# 519_jetson_nano_020001.net
KiCad netlist of a schematic drawn in EAGLE
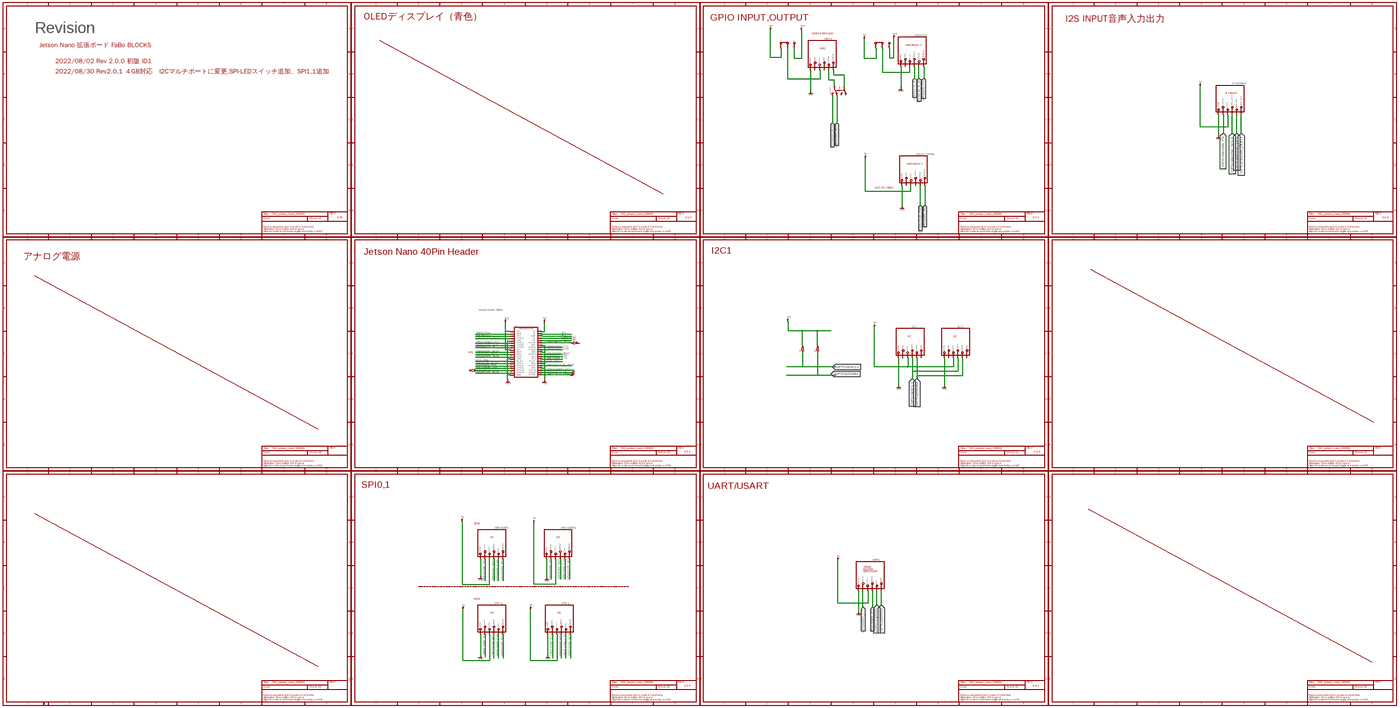
[diagram p0: schematic, sheet 1, overview]
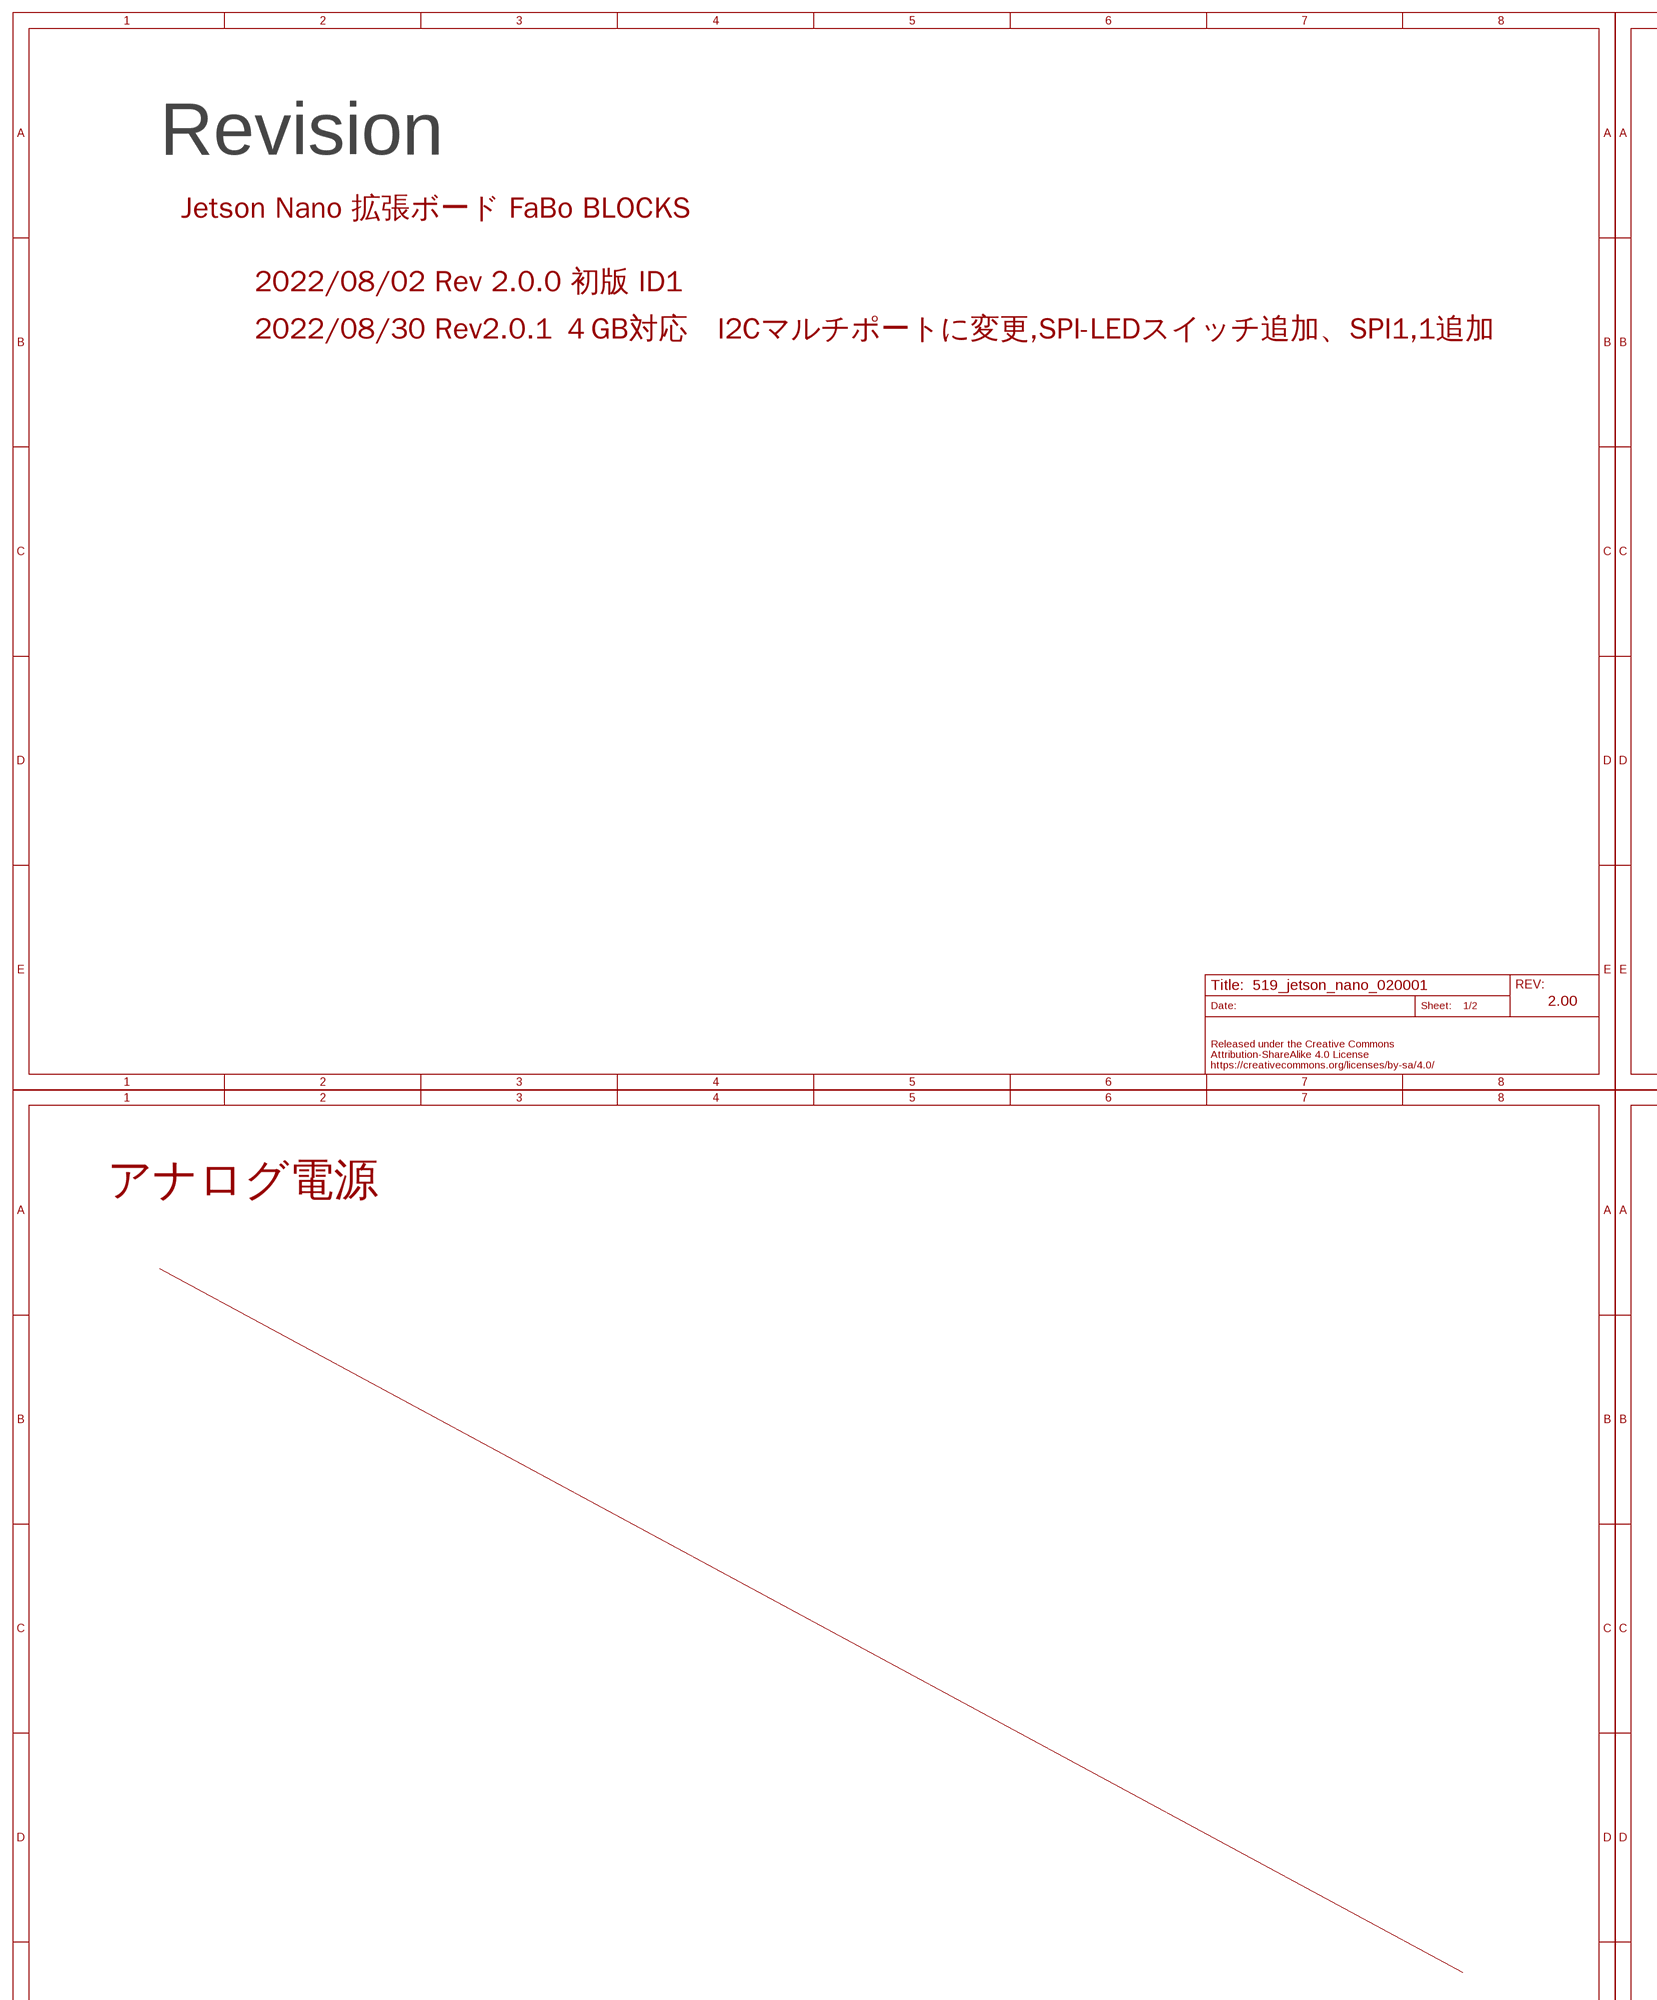
[diagram p1: schematic, sheet 1, part 1 of 8]
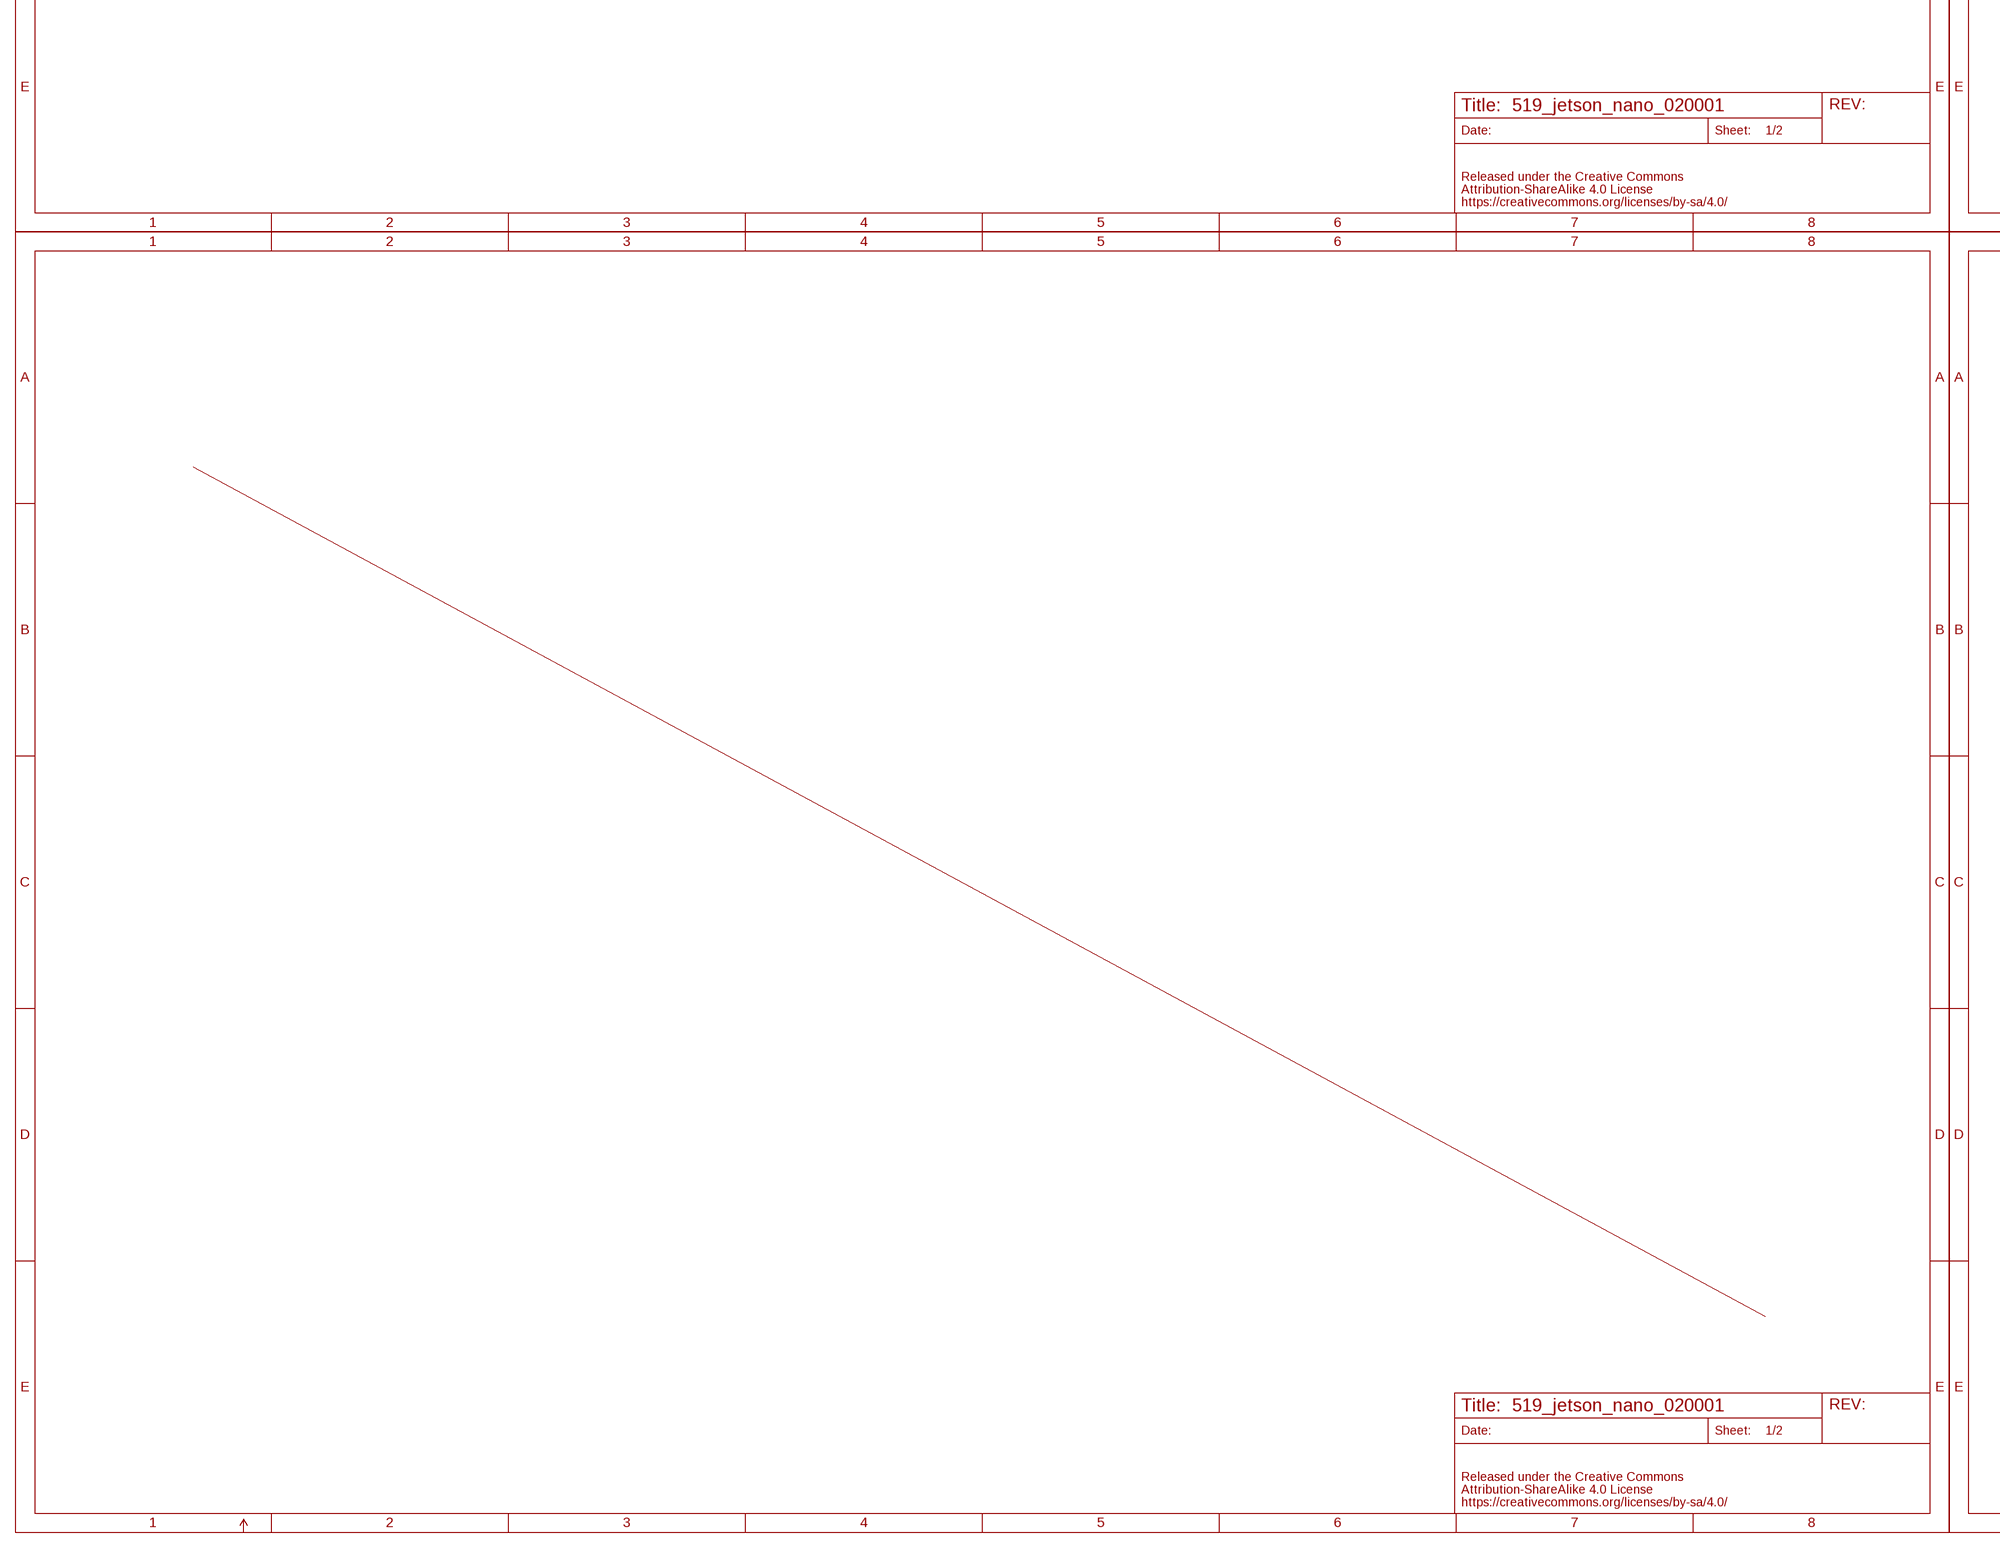
[diagram p2: schematic, sheet 1, part 2 of 8]
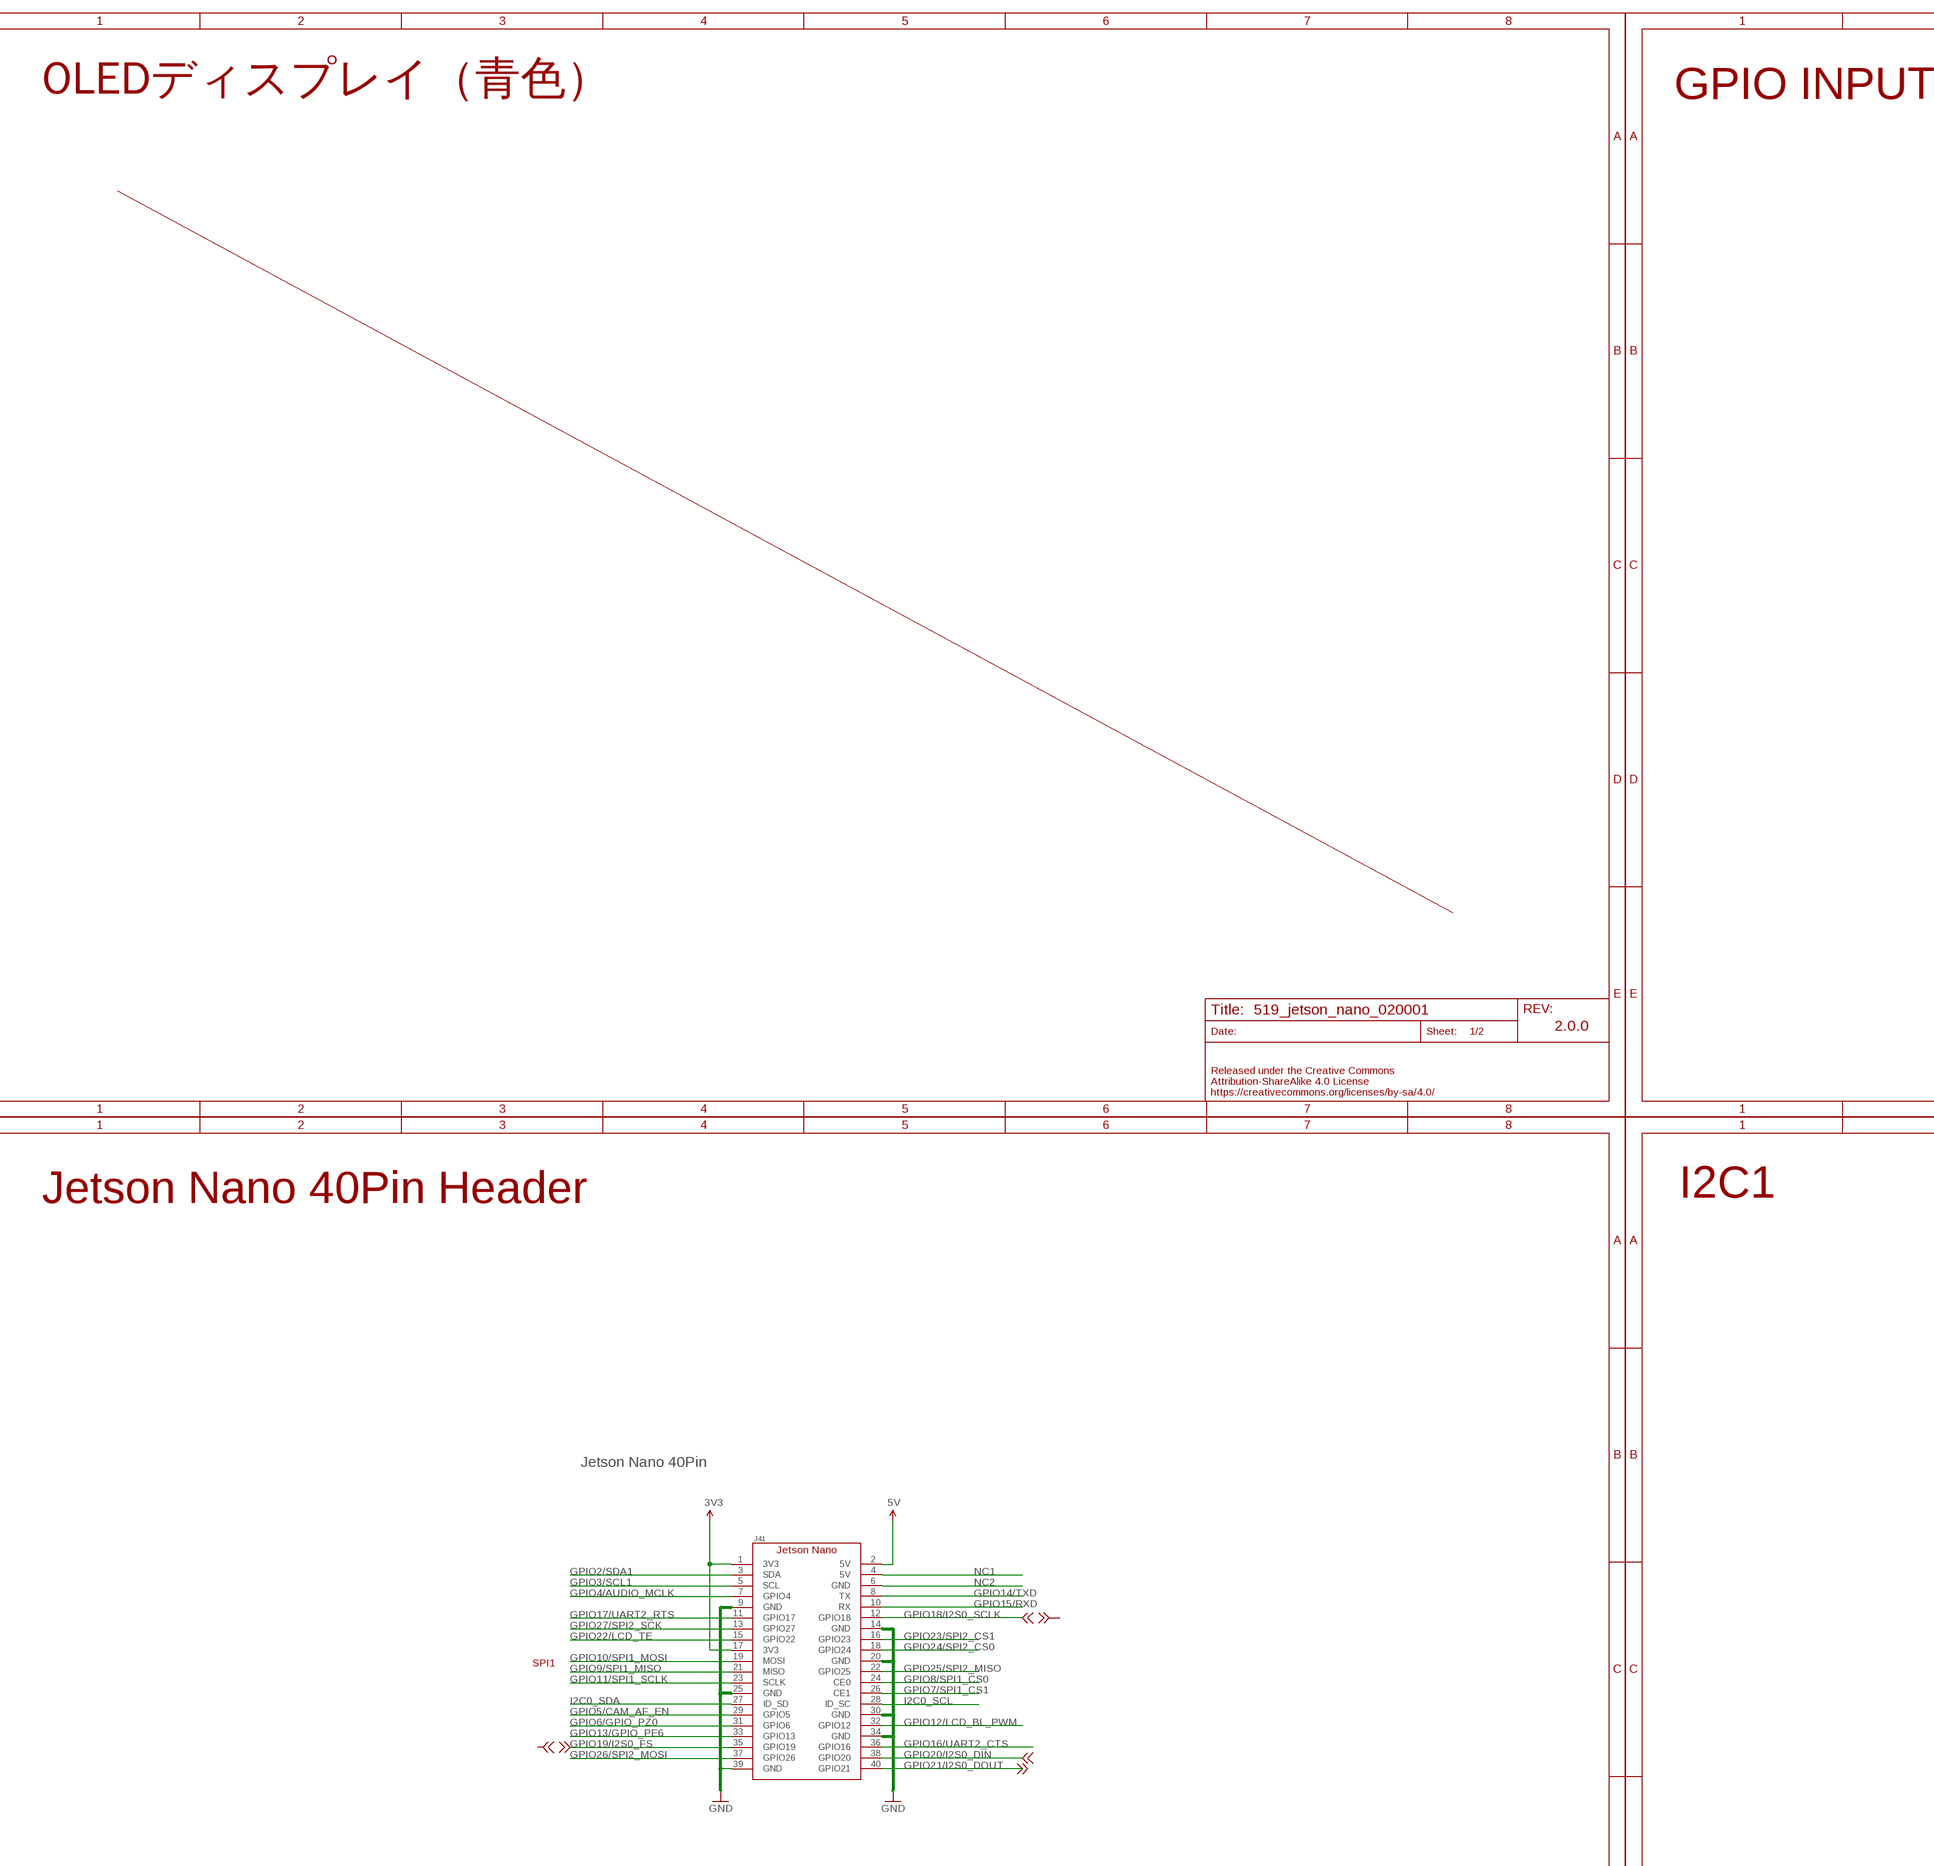
[diagram p3: schematic, sheet 1, part 3 of 8]
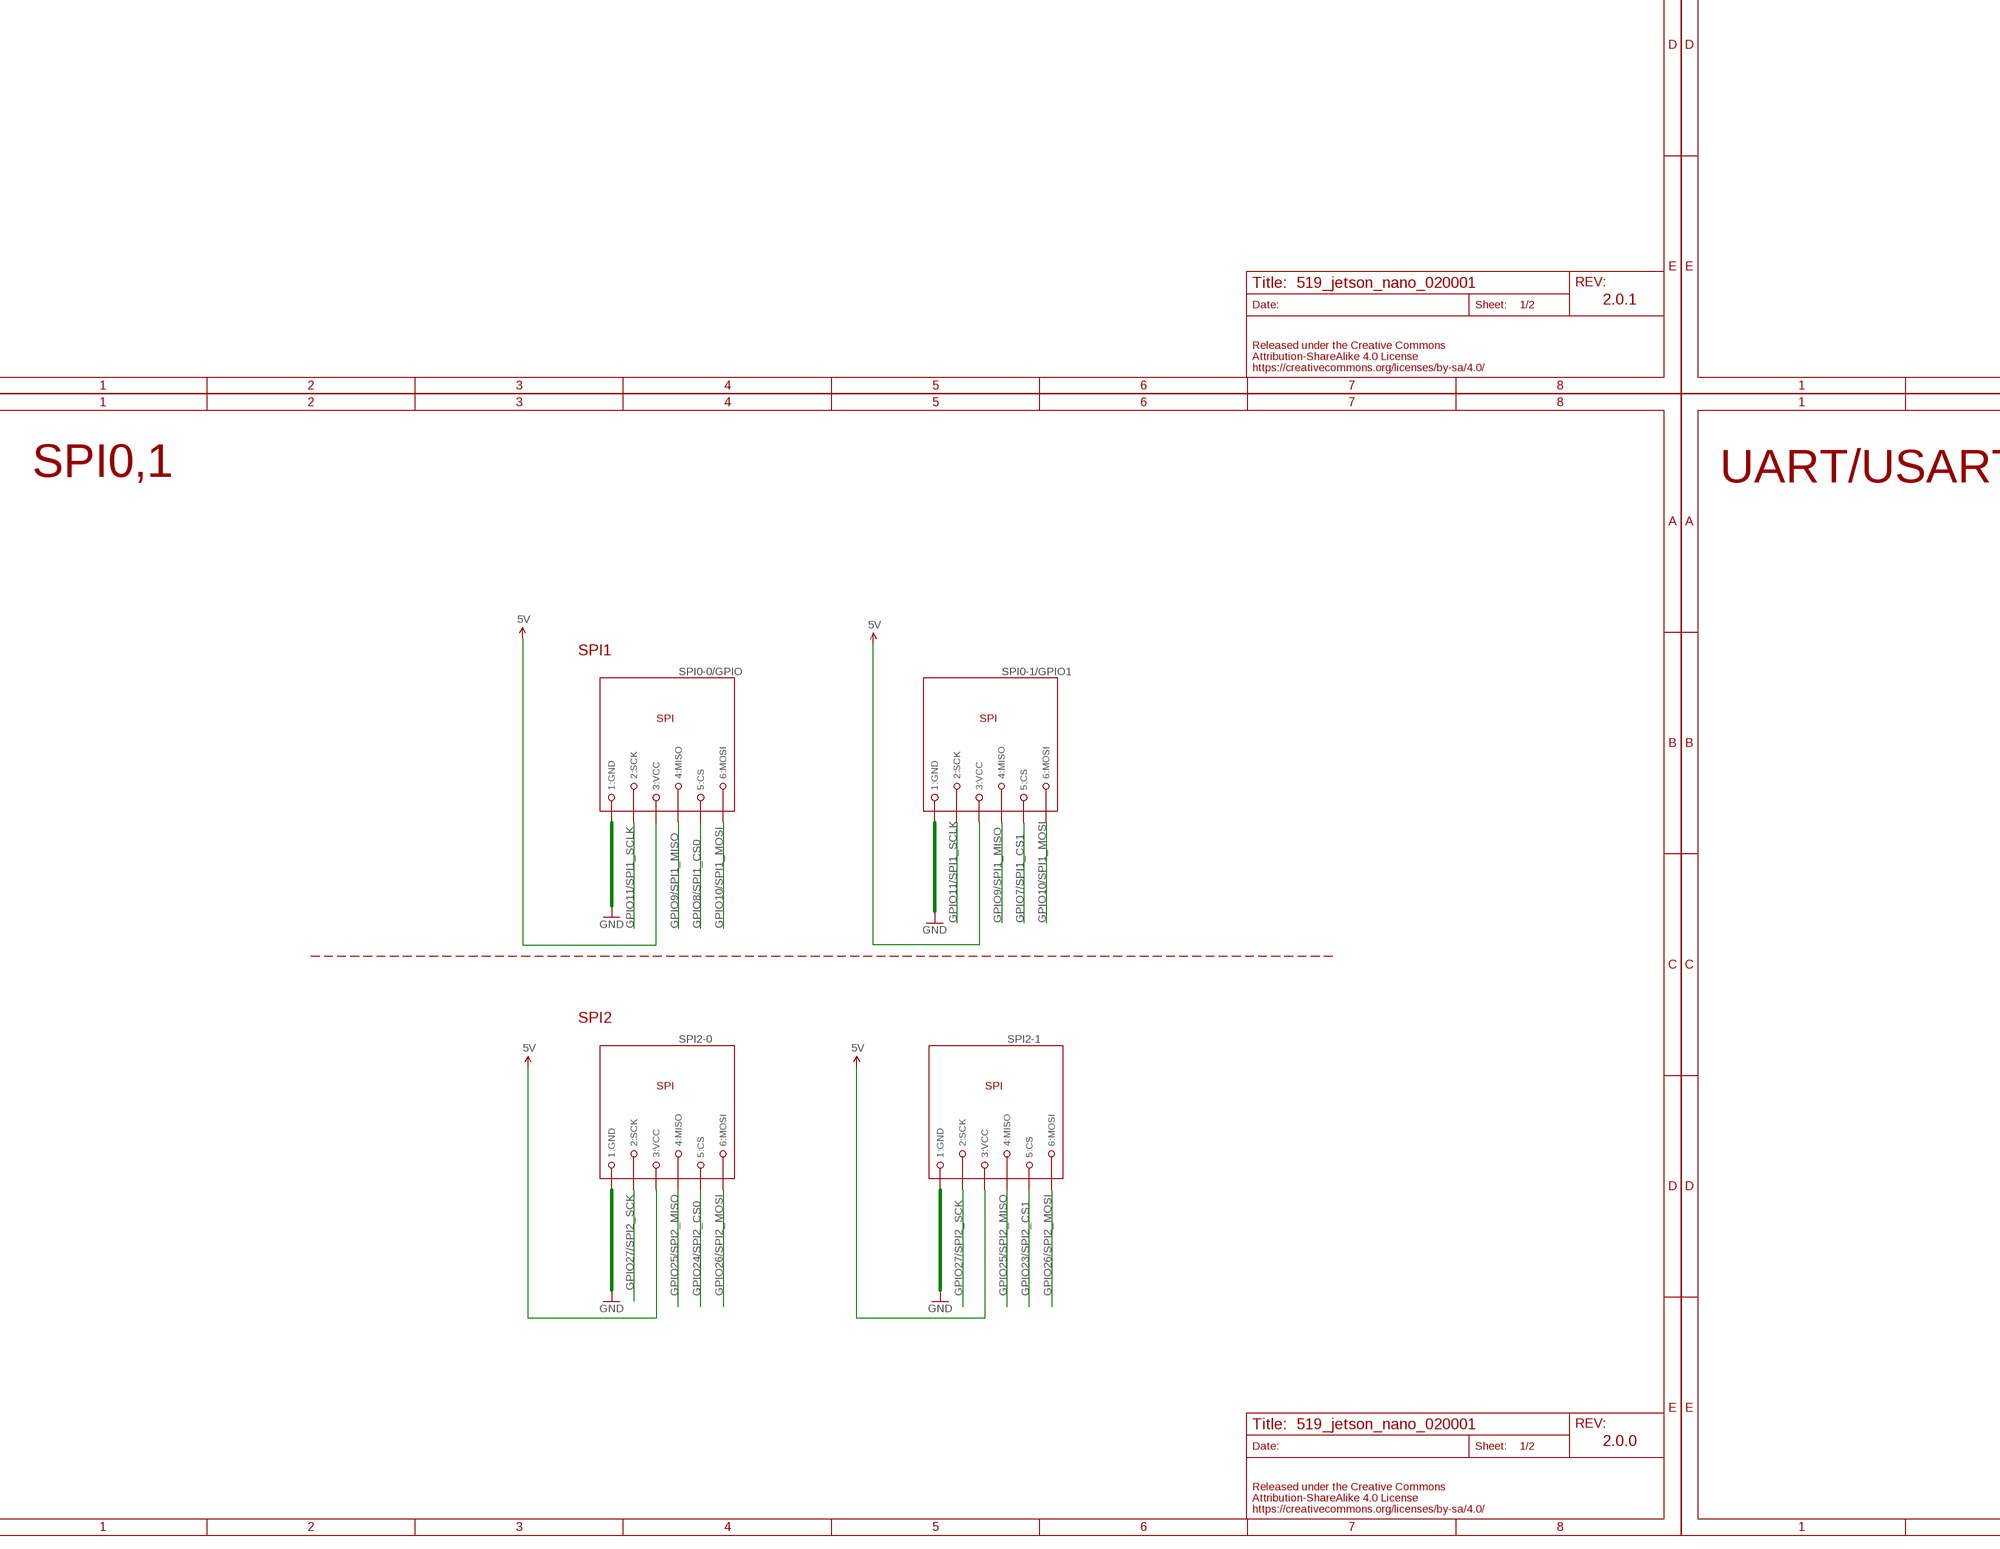
[diagram p4: schematic, sheet 1, part 4 of 8]
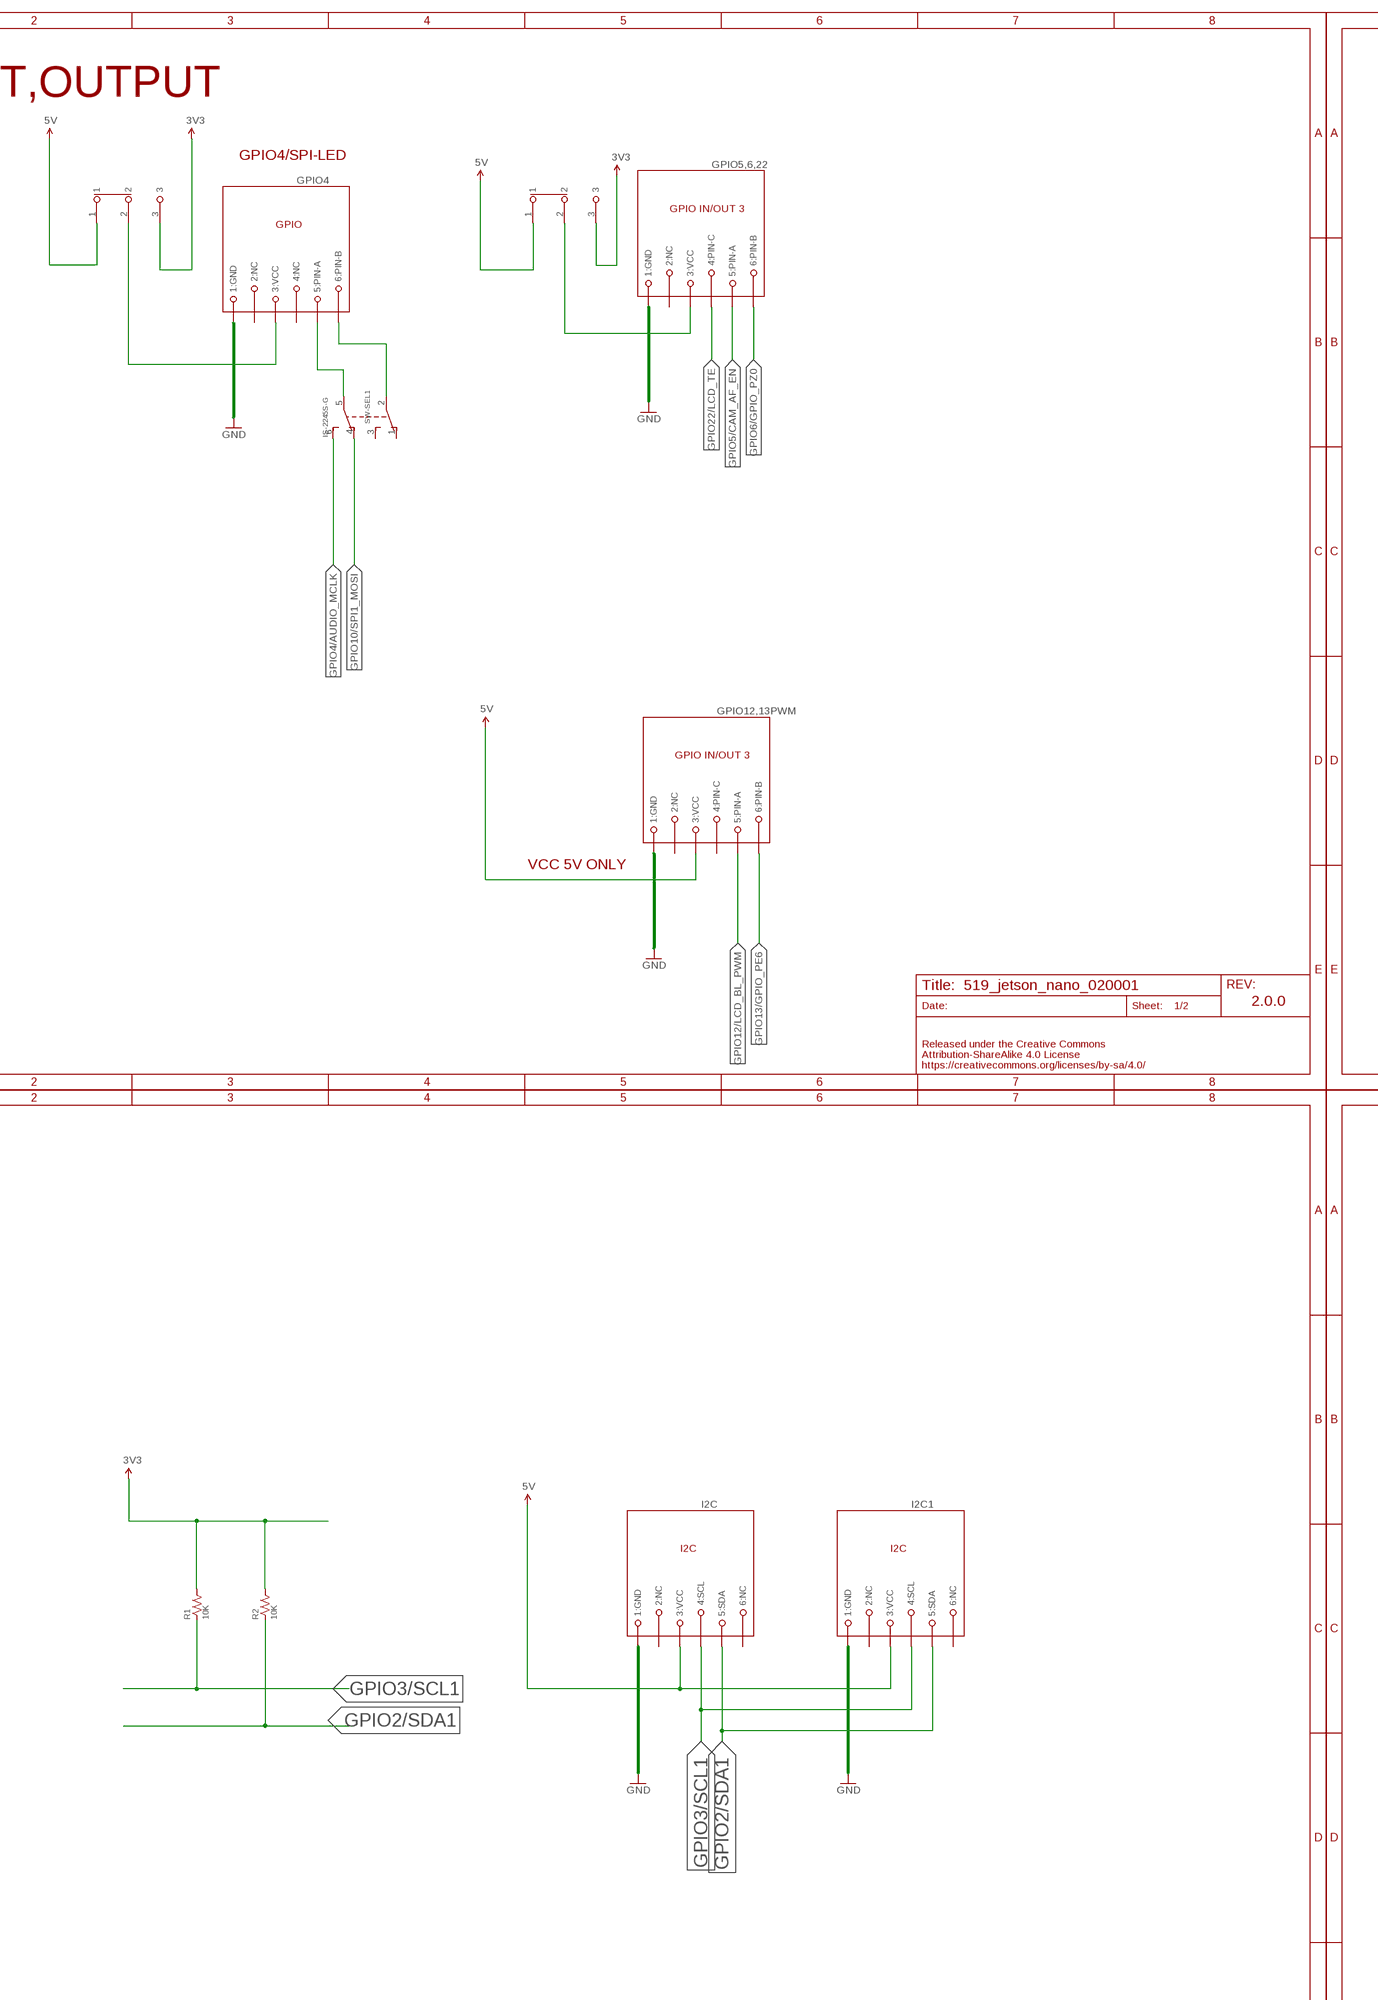
[diagram p5: schematic, sheet 1, part 5 of 8]
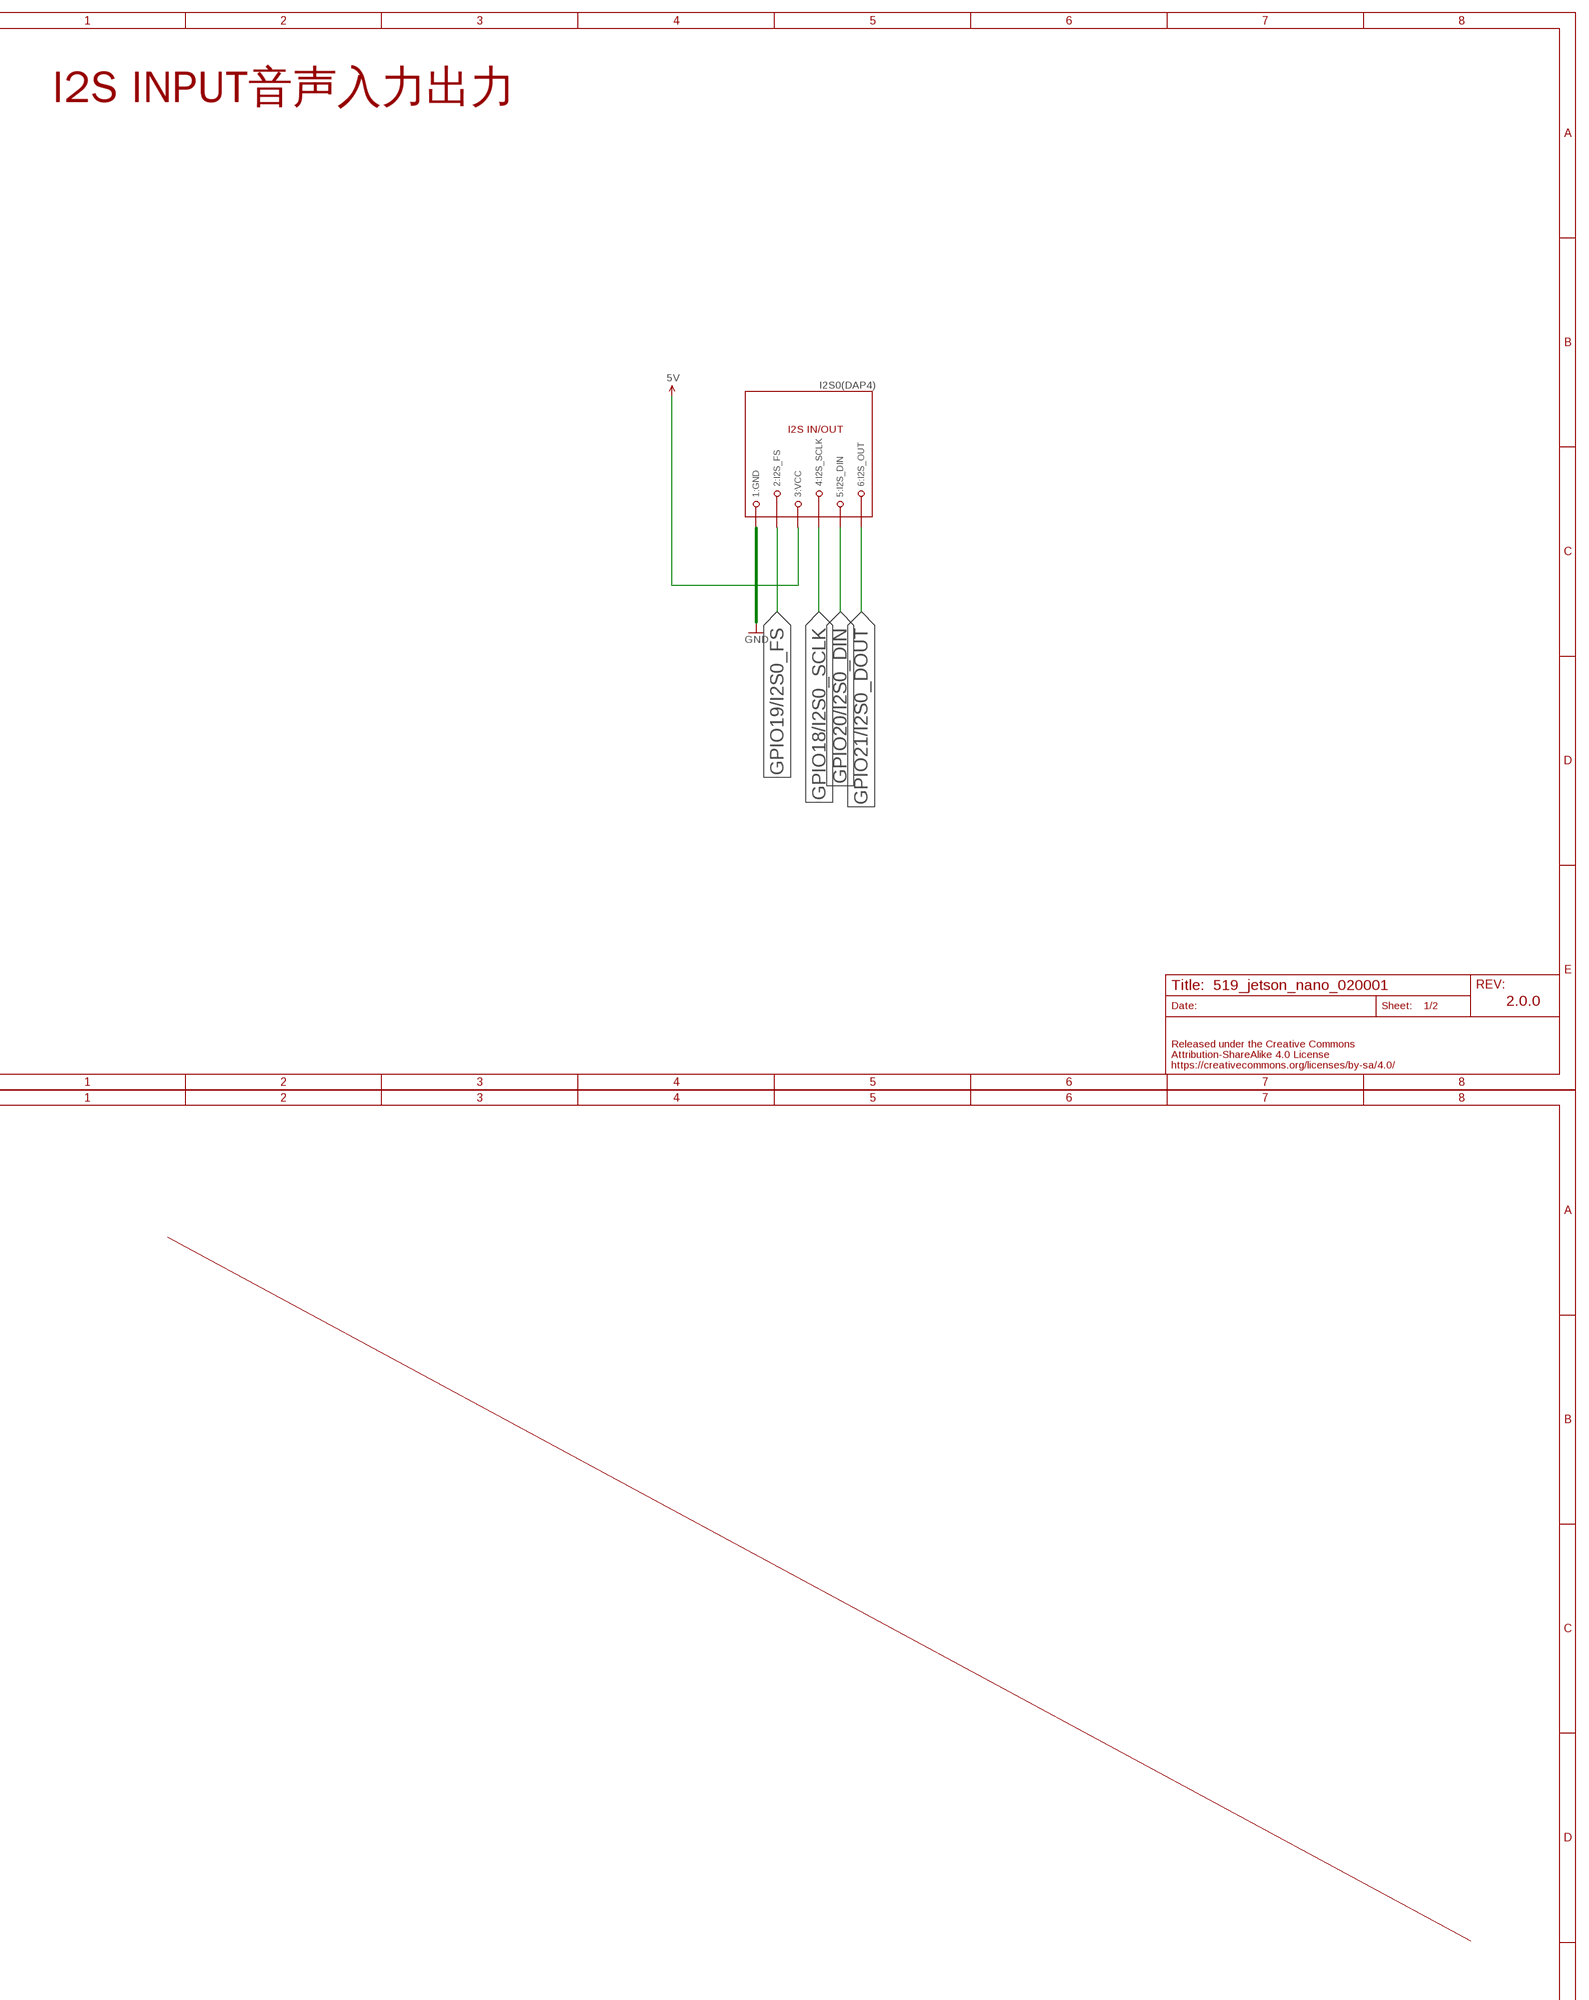
[diagram p6: schematic, sheet 1, part 6 of 8]
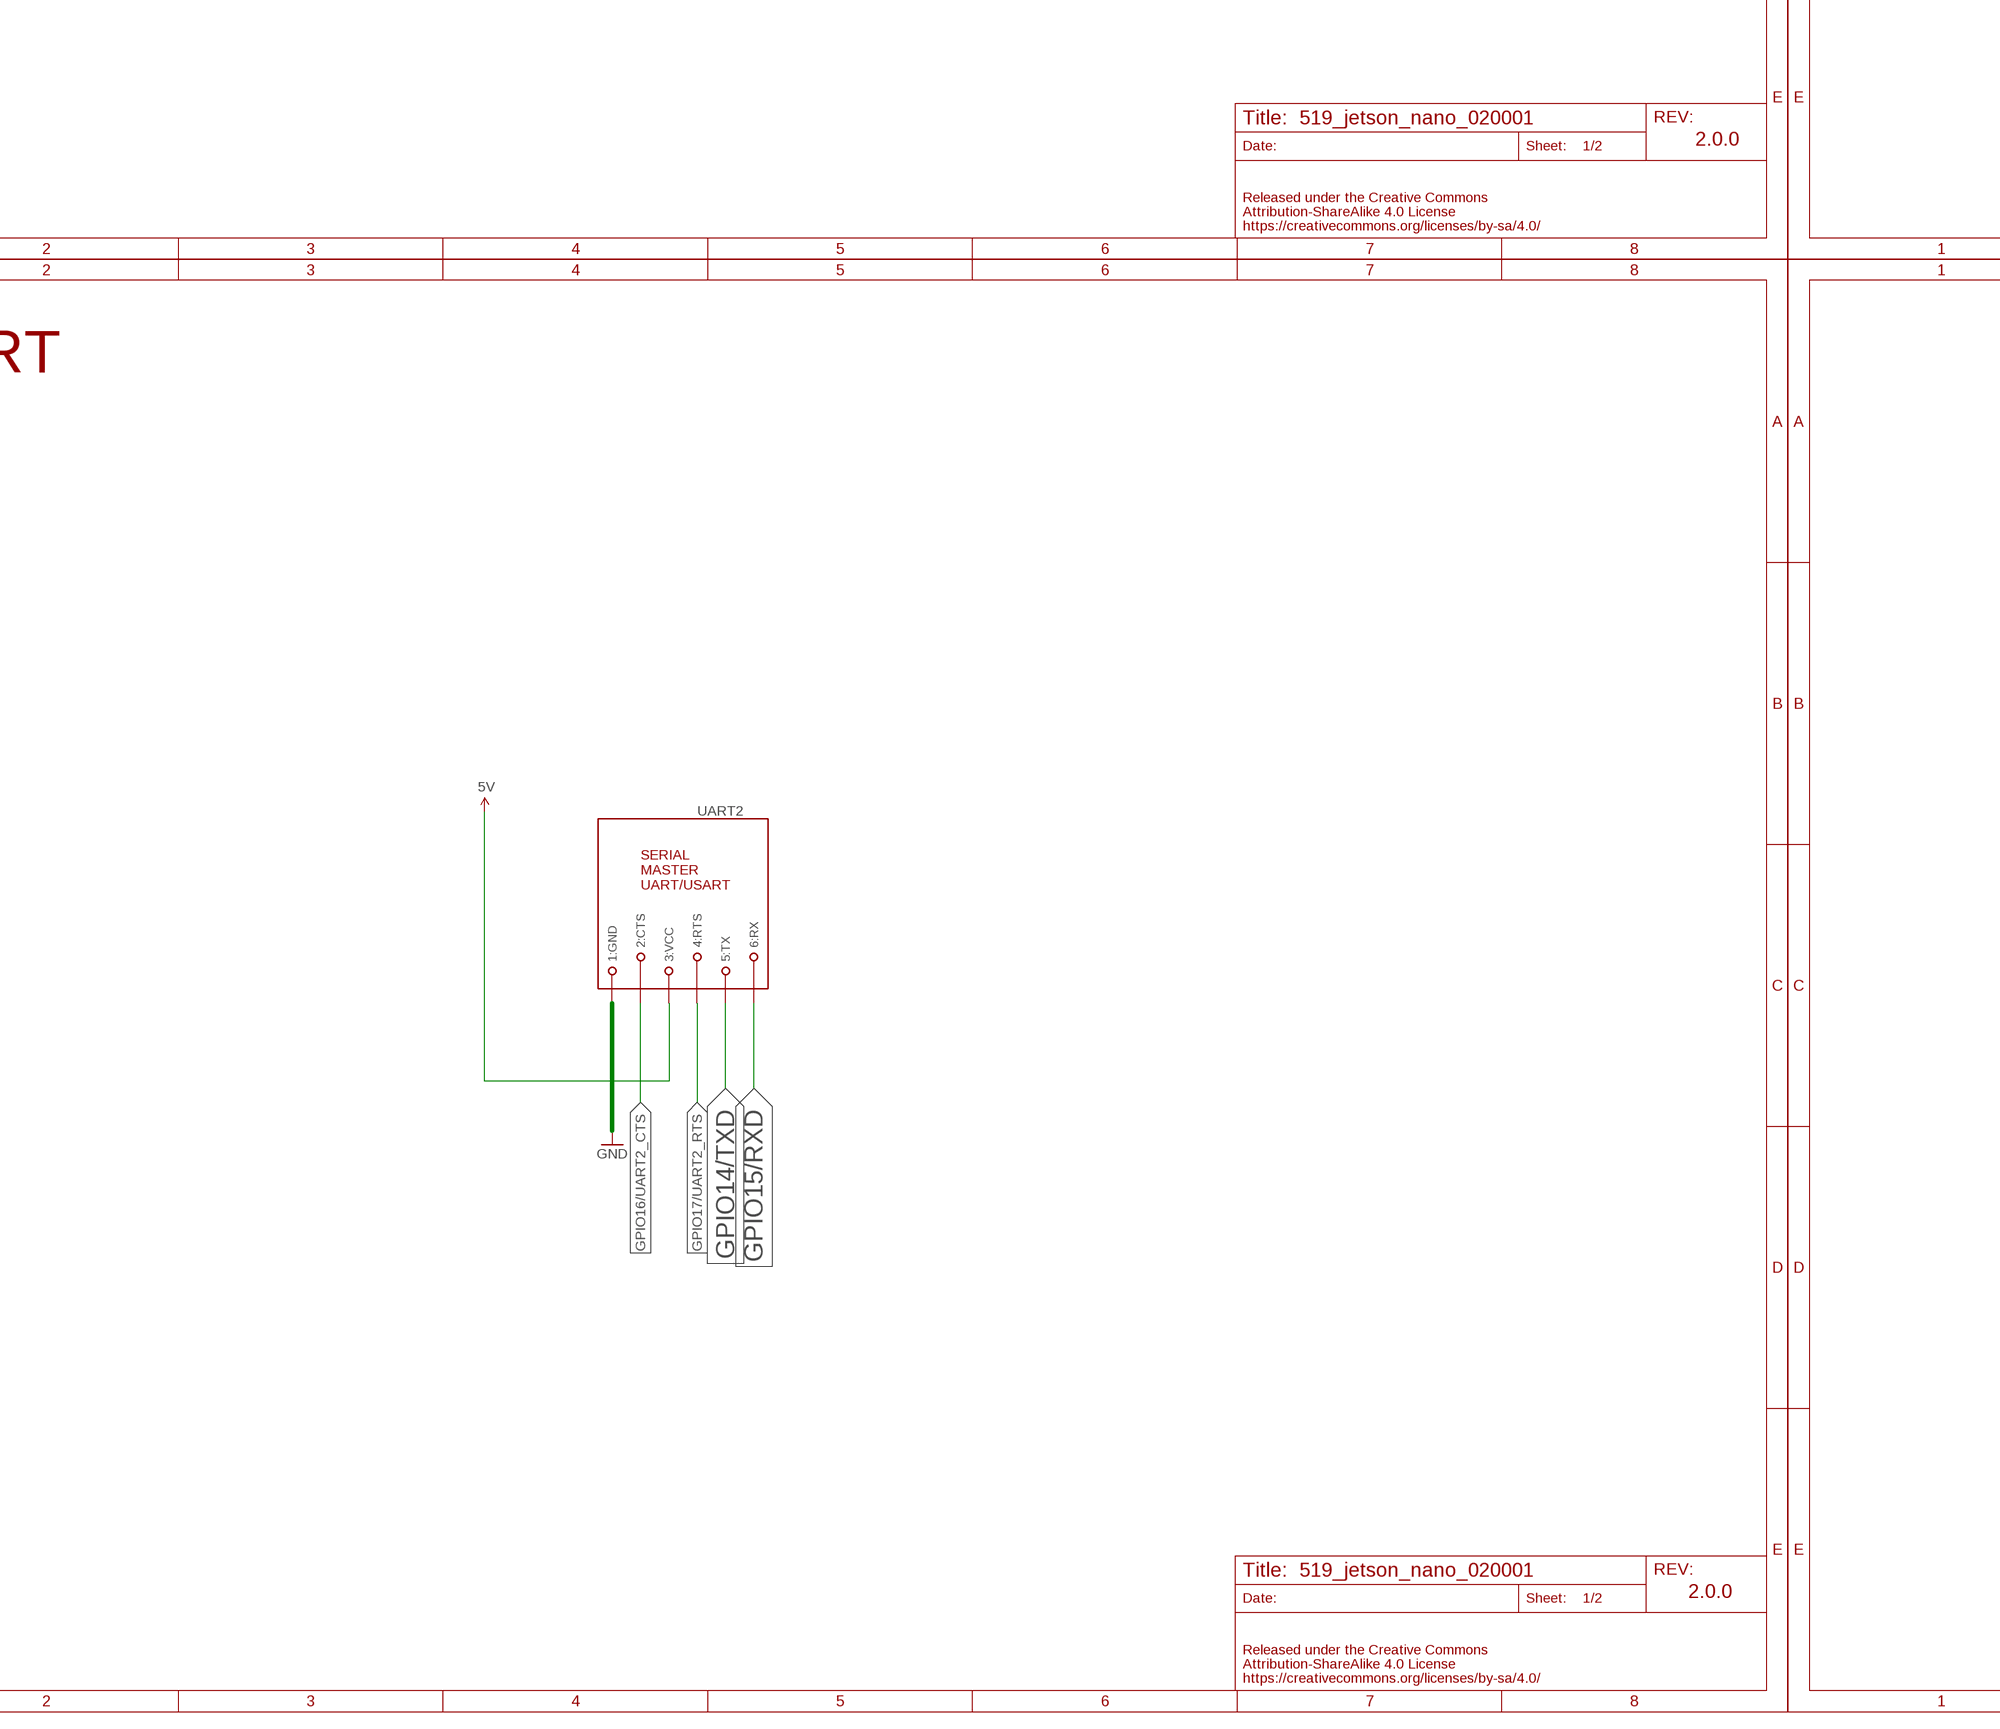
[diagram p7: schematic, sheet 1, part 7 of 8]
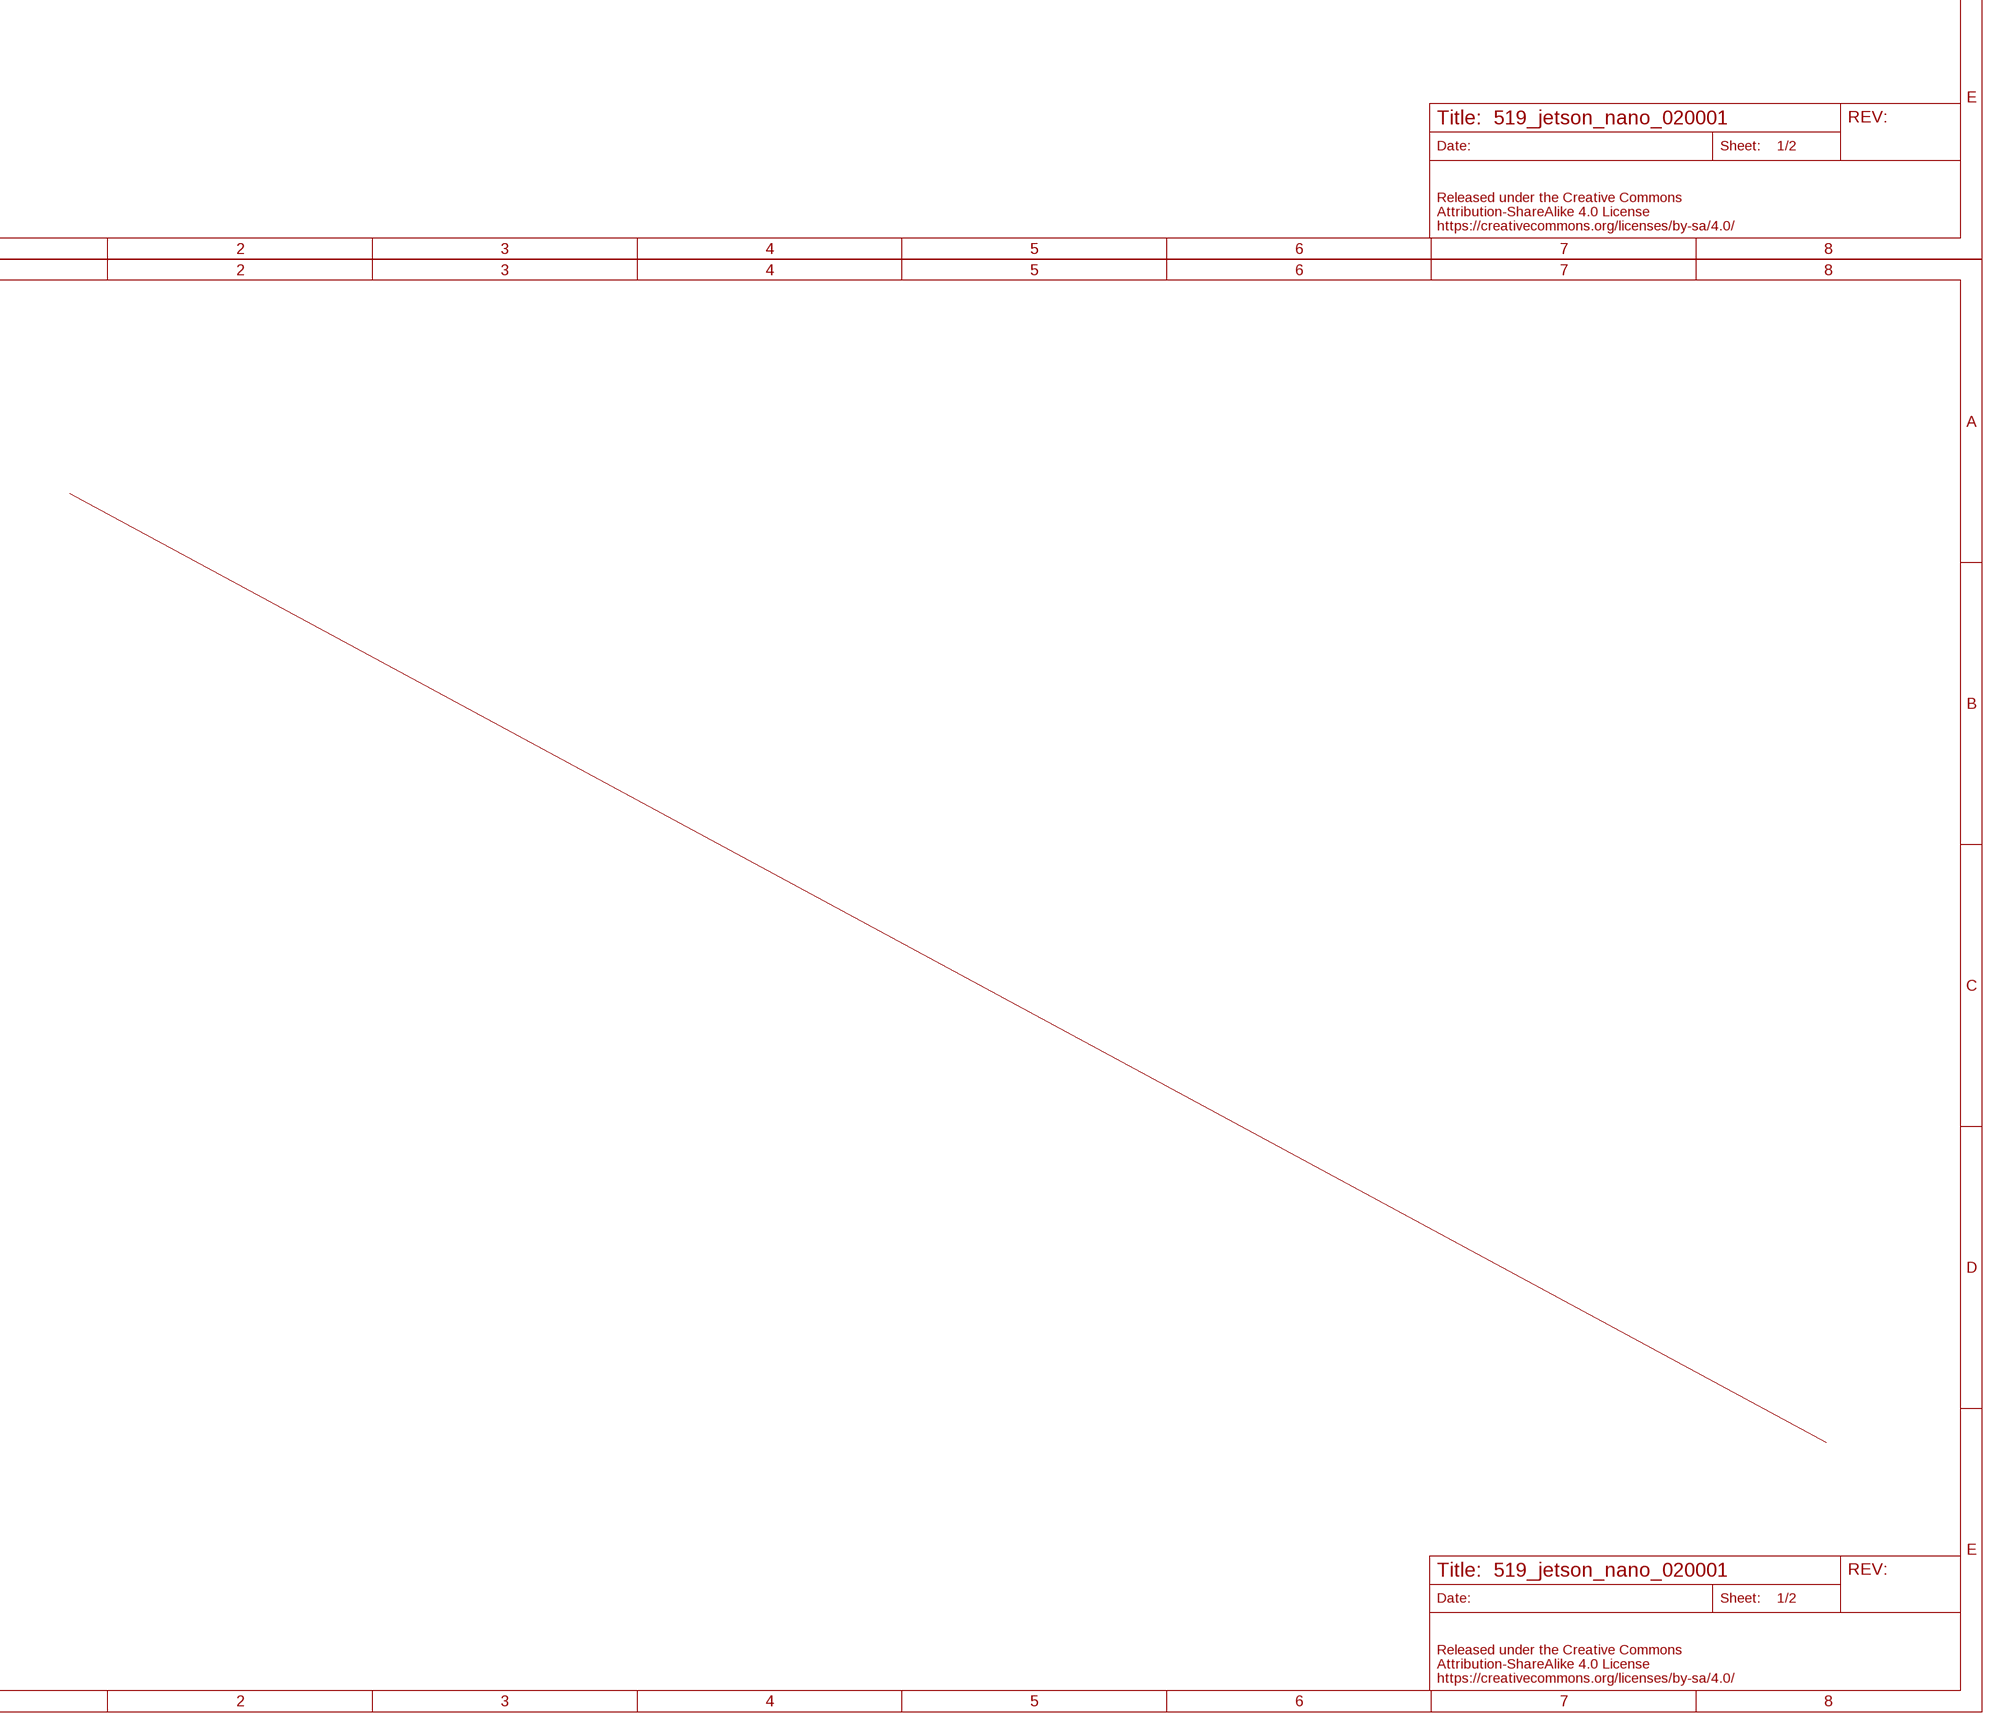
[diagram p8: schematic, sheet 1, part 8 of 8]
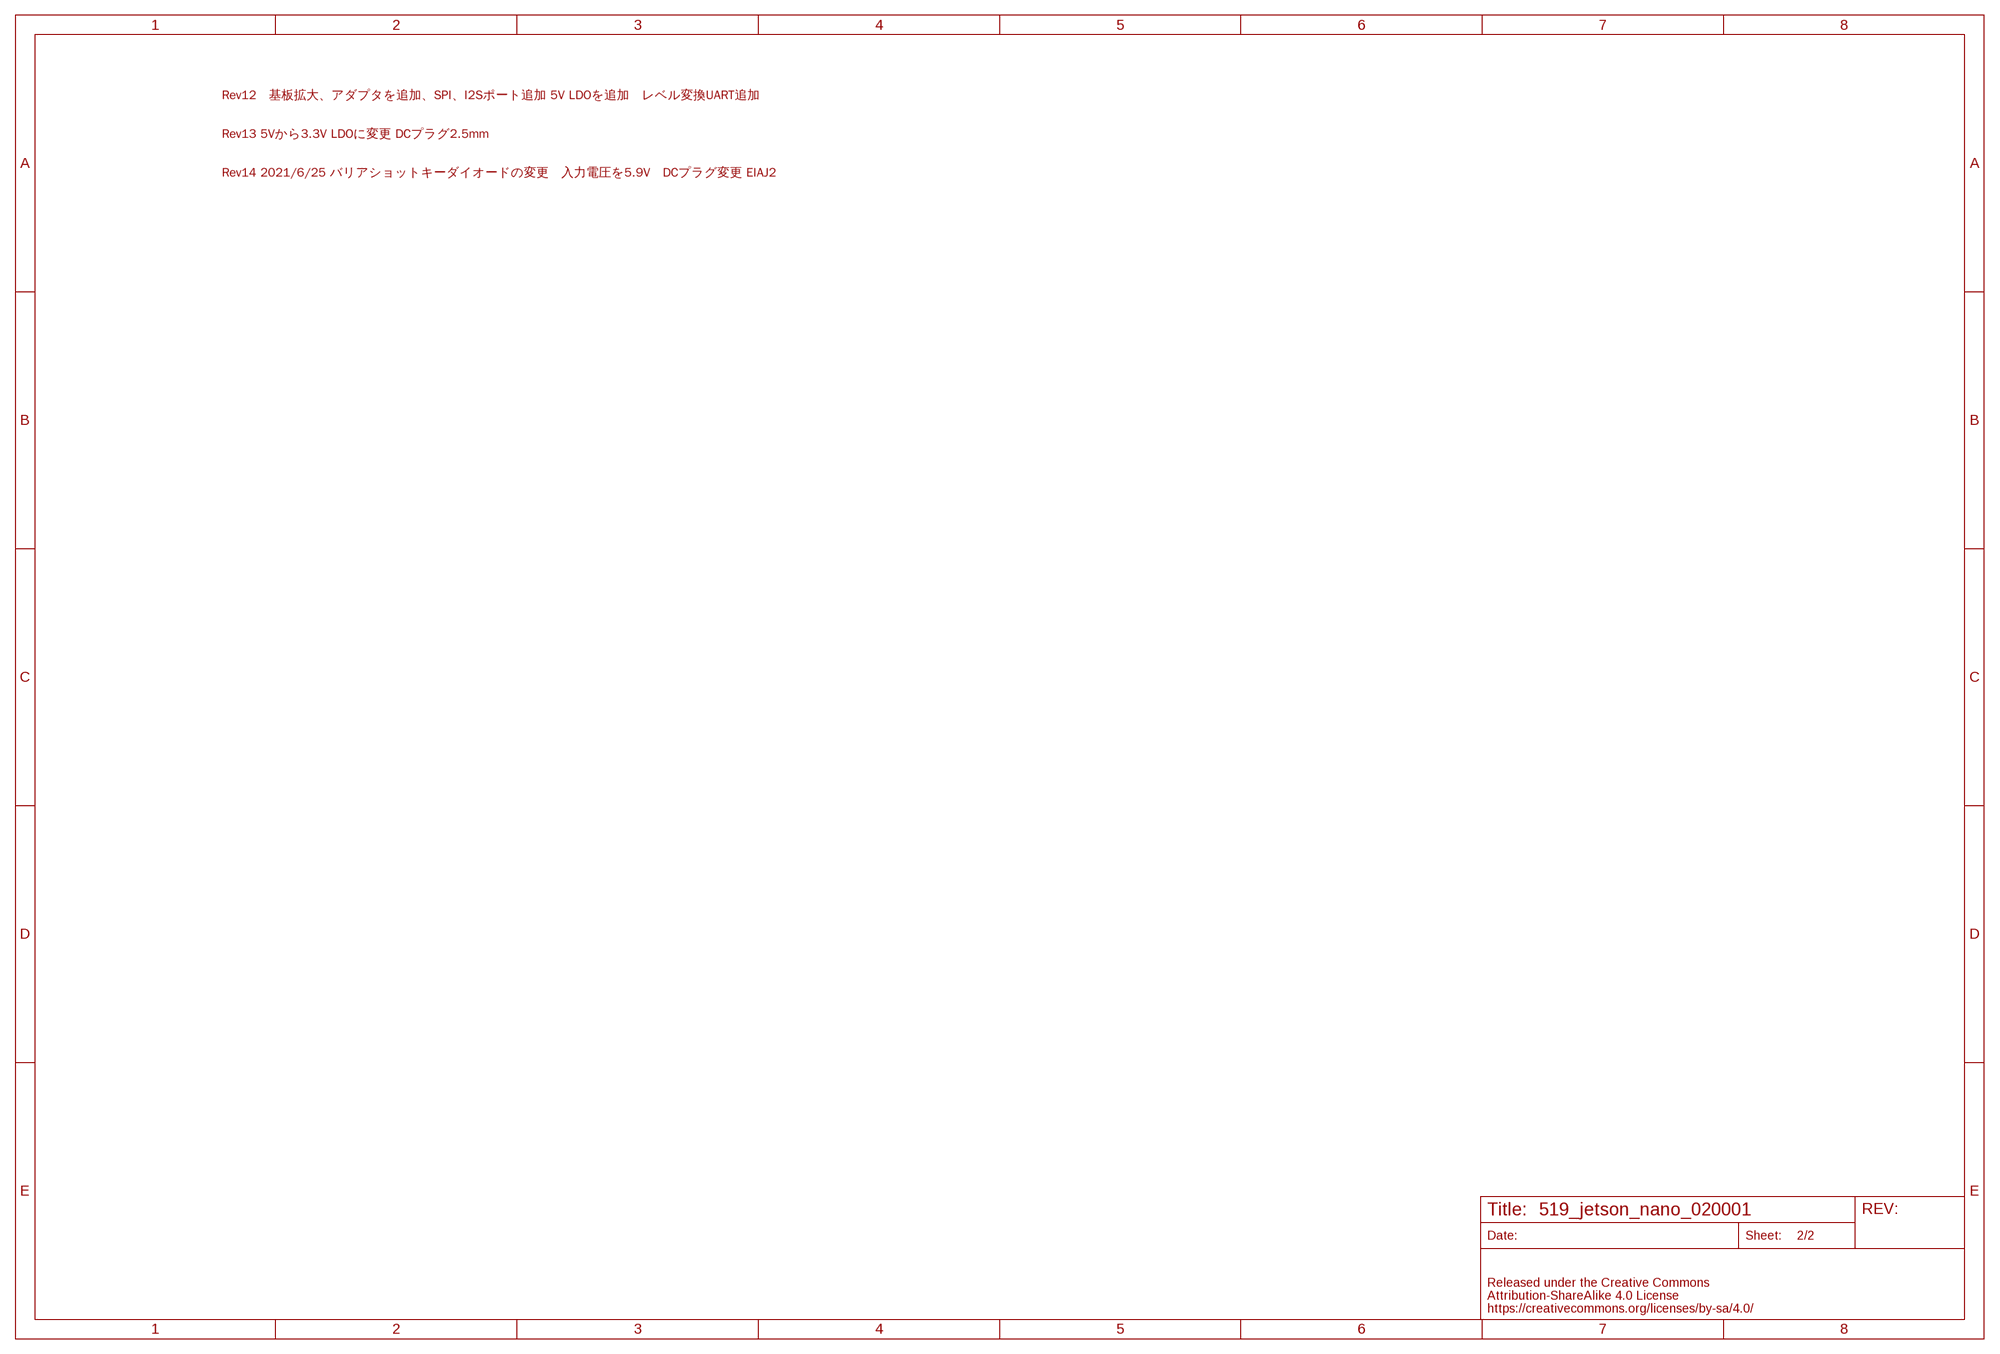
[diagram p9: schematic, sheet 2]

(export (version "E")
  (design (tool "Eeschema 10.0.6"))
  (components
    (comp (ref "GPIO4")
      (value "MODULAR-JACK-6P-RJ11_GPIO")
      (footprint "eagle-import:7002-6PXC-X")
      (libsource (lib "eagle-import") (part "MODULAR-JACK-6P-RJ11_GPIO"))
    )
    (comp (ref "GPIO5,6,22")
      (value "MODULAR-JACK-6P-RJ11_GPIO3")
      (footprint "eagle-import:7002-6PXC-X")
      (libsource (lib "eagle-import") (part "MODULAR-JACK-6P-RJ11_GPIO3"))
    )
    (comp (ref "GPIO12,13PWM")
      (value "MODULAR-JACK-6P-RJ11_GPIO3")
      (footprint "eagle-import:7002-6PXC-X")
      (libsource (lib "eagle-import") (part "MODULAR-JACK-6P-RJ11_GPIO3"))
    )
    (comp (ref "I2C")
      (value "MODULAR-JACK-6P-RJ11_I2C")
      (footprint "eagle-import:7002-6PXC-X")
      (libsource (lib "eagle-import") (part "MODULAR-JACK-6P-RJ11_I2C"))
    )
    (comp (ref "I2C1")
      (value "MODULAR-JACK-6P-RJ11_I2C")
      (footprint "eagle-import:7002-6PXC-X")
      (libsource (lib "eagle-import") (part "MODULAR-JACK-6P-RJ11_I2C"))
    )
    (comp (ref "I2S0(DAP4)")
      (value "MODULAR-JACK-6P-RJ11_I2S_MASTER")
      (footprint "eagle-import:7002-6PXC-X")
      (libsource (lib "eagle-import") (part "MODULAR-JACK-6P-RJ11_I2S_MASTER"))
    )
    (comp (ref "J41")
      (value "JETSON_NANOJETSON_NANO_OVERALL")
      (footprint "eagle-import:JETSON_NANO_DEMENTION")
      (libsource (lib "eagle-import") (part "JETSON_NANOJETSON_NANO_OVERALL"))
    )
    (comp (ref "R1")
      (value "10K")
      (footprint "eagle-import:0402")
      (libsource (lib "eagle-import") (part "RESISTOR-0402"))
    )
    (comp (ref "R2")
      (value "10K")
      (footprint "eagle-import:0402")
      (libsource (lib "eagle-import") (part "RESISTOR-0402"))
    )
    (comp (ref "SPI0-0/GPIO")
      (value "MODULAR-JACK-6P-RJ11_SPI")
      (footprint "eagle-import:7002-6PXC-X")
      (libsource (lib "eagle-import") (part "MODULAR-JACK-6P-RJ11_SPI"))
    )
    (comp (ref "SPI0-1/GPIO1")
      (value "MODULAR-JACK-6P-RJ11_SPI")
      (footprint "eagle-import:7002-6PXC-X")
      (libsource (lib "eagle-import") (part "MODULAR-JACK-6P-RJ11_SPI"))
    )
    (comp (ref "SPI2-0")
      (value "MODULAR-JACK-6P-RJ11_SPI")
      (footprint "eagle-import:7002-6PXC-X")
      (libsource (lib "eagle-import") (part "MODULAR-JACK-6P-RJ11_SPI"))
    )
    (comp (ref "SPI2-1")
      (value "MODULAR-JACK-6P-RJ11_SPI")
      (footprint "eagle-import:7002-6PXC-X")
      (libsource (lib "eagle-import") (part "MODULAR-JACK-6P-RJ11_SPI"))
    )
    (comp (ref "SW-SEL1")
      (value "IS-2245S-G")
      (footprint "eagle-import:IS-2245S-G")
      (libsource (lib "eagle-import") (part "IS-2245S-G"))
    )
    (comp (ref "U$3")
      (value "SSSS213202")
      (footprint "eagle-import:SSSS213202")
      (libsource (lib "eagle-import") (part "SSSS213202"))
    )
    (comp (ref "U$32")
      (value "SSSS213202")
      (footprint "eagle-import:SSSS213202")
      (libsource (lib "eagle-import") (part "SSSS213202"))
    )
    (comp (ref "UART2")
      (value "MODULAR-JACK-6P-RJ11_SERIAL_M_USART")
      (footprint "eagle-import:7002-6PXC-X")
      (libsource (lib "eagle-import") (part "MODULAR-JACK-6P-RJ11_SERIAL_M_USART"))
    )
  )
  (nets
    (net (code "1") (name "3V3") (class "Default")
      (node (ref "J41") (pin "1") (pinfunction "3V3_1") (pintype "bidirectional"))
      (node (ref "J41") (pin "17") (pinfunction "3V3_17") (pintype "bidirectional"))
      (node (ref "R1") (pin "2") (pinfunction "2_2") (pintype "bidirectional"))
      (node (ref "R2") (pin "2") (pinfunction "2_2") (pintype "bidirectional"))
      (node (ref "U$3") (pin "3") (pinfunction "3_3") (pintype "bidirectional"))
      (node (ref "U$32") (pin "3") (pinfunction "3_3") (pintype "bidirectional"))
    )
    (net (code "2") (name "5V") (class "Default")
      (node (ref "GPIO12,13PWM") (pin "3") (pinfunction "3:VCC_3") (pintype "power_in"))
      (node (ref "I2C") (pin "3") (pinfunction "3:VCC_3") (pintype "power_in"))
      (node (ref "I2C1") (pin "3") (pinfunction "3:VCC_3") (pintype "power_in"))
      (node (ref "I2S0(DAP4)") (pin "3") (pinfunction "3:VCC_3") (pintype "power_in"))
      (node (ref "J41") (pin "2") (pinfunction "5V_2") (pintype "bidirectional"))
      (node (ref "SPI0-0/GPIO") (pin "3") (pinfunction "3:VCC_3") (pintype "power_in"))
      (node (ref "SPI0-1/GPIO1") (pin "3") (pinfunction "3:VCC_3") (pintype "power_in"))
      (node (ref "SPI2-0") (pin "3") (pinfunction "3:VCC_3") (pintype "power_in"))
      (node (ref "SPI2-1") (pin "3") (pinfunction "3:VCC_3") (pintype "power_in"))
      (node (ref "U$3") (pin "1") (pinfunction "1_1") (pintype "bidirectional"))
      (node (ref "U$32") (pin "1") (pinfunction "1_1") (pintype "bidirectional"))
      (node (ref "UART2") (pin "3") (pinfunction "3:VCC_3") (pintype "power_in"))
    )
    (net (code "3") (name "GND") (class "Default")
      (node (ref "GPIO12,13PWM") (pin "1") (pinfunction "1:GND_1") (pintype "power_in"))
      (node (ref "GPIO4") (pin "1") (pinfunction "1:GND_1") (pintype "power_in"))
      (node (ref "GPIO5,6,22") (pin "1") (pinfunction "1:GND_1") (pintype "power_in"))
      (node (ref "I2C") (pin "1") (pinfunction "1:GND_1") (pintype "power_in"))
      (node (ref "I2C1") (pin "1") (pinfunction "1:GND_1") (pintype "power_in"))
      (node (ref "I2S0(DAP4)") (pin "1") (pinfunction "1:GND_1") (pintype "power_in"))
      (node (ref "J41") (pin "14") (pinfunction "GND_14") (pintype "bidirectional"))
      (node (ref "J41") (pin "20") (pinfunction "GND_20") (pintype "bidirectional"))
      (node (ref "J41") (pin "25") (pinfunction "GND_25") (pintype "bidirectional"))
      (node (ref "J41") (pin "30") (pinfunction "GND_30") (pintype "bidirectional"))
      (node (ref "J41") (pin "34") (pinfunction "GND_34") (pintype "bidirectional"))
      (node (ref "J41") (pin "39") (pinfunction "GND_39") (pintype "bidirectional"))
      (node (ref "J41") (pin "9") (pinfunction "GND_9") (pintype "bidirectional"))
      (node (ref "SPI0-0/GPIO") (pin "1") (pinfunction "1:GND_1") (pintype "power_in"))
      (node (ref "SPI0-1/GPIO1") (pin "1") (pinfunction "1:GND_1") (pintype "power_in"))
      (node (ref "SPI2-0") (pin "1") (pinfunction "1:GND_1") (pintype "power_in"))
      (node (ref "SPI2-1") (pin "1") (pinfunction "1:GND_1") (pintype "power_in"))
      (node (ref "UART2") (pin "1") (pinfunction "1:GND_1") (pintype "power_in"))
    )
    (net (code "4") (name "GPIO2{slash}SDA1") (class "Default")
      (node (ref "I2C") (pin "5") (pinfunction "5:SDA_5") (pintype "open_collector"))
      (node (ref "I2C1") (pin "5") (pinfunction "5:SDA_5") (pintype "open_collector"))
      (node (ref "J41") (pin "3") (pinfunction "SDA_3") (pintype "bidirectional"))
      (node (ref "R2") (pin "1") (pinfunction "1_1") (pintype "bidirectional"))
    )
    (net (code "5") (name "GPIO3{slash}SCL1") (class "Default")
      (node (ref "I2C") (pin "4") (pinfunction "4:SCL_4") (pintype "open_collector"))
      (node (ref "I2C1") (pin "4") (pinfunction "4:SCL_4") (pintype "open_collector"))
      (node (ref "J41") (pin "5") (pinfunction "SCL_5") (pintype "bidirectional"))
      (node (ref "R1") (pin "1") (pinfunction "1_1") (pintype "bidirectional"))
    )
    (net (code "6") (name "GPIO4{slash}AUDIO_MCLK") (class "Default")
      (node (ref "J41") (pin "7") (pinfunction "GPIO4_7") (pintype "bidirectional"))
      (node (ref "SW-SEL1") (pin "6") (pinfunction "6_6") (pintype "passive"))
    )
    (net (code "7") (name "GPIO5{slash}CAM_AF_EN") (class "Default")
      (node (ref "GPIO5,6,22") (pin "5") (pinfunction "5:PIN-A_5") (pintype "bidirectional"))
      (node (ref "J41") (pin "29") (pinfunction "GPIO5_29") (pintype "bidirectional"))
    )
    (net (code "8") (name "GPIO6{slash}GPIO_PZ0") (class "Default")
      (node (ref "GPIO5,6,22") (pin "6") (pinfunction "6:PIN-B_6") (pintype "bidirectional"))
      (node (ref "J41") (pin "31") (pinfunction "GPIO6_31") (pintype "bidirectional"))
    )
    (net (code "9") (name "GPIO7{slash}SPI1_CS1") (class "Default")
      (node (ref "J41") (pin "26") (pinfunction "CE1_26") (pintype "bidirectional"))
      (node (ref "SPI0-1/GPIO1") (pin "5") (pinfunction "5:CS_5") (pintype "open_collector"))
    )
    (net (code "10") (name "GPIO8{slash}SPI1_CS0") (class "Default")
      (node (ref "J41") (pin "24") (pinfunction "CE0_24") (pintype "bidirectional"))
      (node (ref "SPI0-0/GPIO") (pin "5") (pinfunction "5:CS_5") (pintype "open_collector"))
    )
    (net (code "11") (name "GPIO9{slash}SPI1_MISO") (class "Default")
      (node (ref "J41") (pin "21") (pinfunction "MISO_21") (pintype "bidirectional"))
      (node (ref "SPI0-0/GPIO") (pin "4") (pinfunction "4:MISO_4") (pintype "open_collector"))
      (node (ref "SPI0-1/GPIO1") (pin "4") (pinfunction "4:MISO_4") (pintype "open_collector"))
    )
    (net (code "12") (name "GPIO10{slash}SPI1_MOSI") (class "Default")
      (node (ref "J41") (pin "19") (pinfunction "MOSI_19") (pintype "bidirectional"))
      (node (ref "SPI0-0/GPIO") (pin "6") (pinfunction "6:MOSI_6") (pintype "open_collector"))
      (node (ref "SPI0-1/GPIO1") (pin "6") (pinfunction "6:MOSI_6") (pintype "open_collector"))
      (node (ref "SW-SEL1") (pin "4") (pinfunction "4_4") (pintype "passive"))
    )
    (net (code "13") (name "GPIO11{slash}SPI1_SCLK") (class "Default")
      (node (ref "J41") (pin "23") (pinfunction "SCLK_23") (pintype "bidirectional"))
      (node (ref "SPI0-0/GPIO") (pin "2") (pinfunction "2:SCK_2") (pintype "open_collector"))
      (node (ref "SPI0-1/GPIO1") (pin "2") (pinfunction "2:SCK_2") (pintype "open_collector"))
    )
    (net (code "14") (name "GPIO12{slash}LCD_BL_PWM") (class "Default")
      (node (ref "GPIO12,13PWM") (pin "5") (pinfunction "5:PIN-A_5") (pintype "bidirectional"))
      (node (ref "J41") (pin "32") (pinfunction "GPIO12_32") (pintype "bidirectional"))
    )
    (net (code "15") (name "GPIO13{slash}GPIO_PE6") (class "Default")
      (node (ref "GPIO12,13PWM") (pin "6") (pinfunction "6:PIN-B_6") (pintype "bidirectional"))
      (node (ref "J41") (pin "33") (pinfunction "GPIO13_33") (pintype "bidirectional"))
    )
    (net (code "16") (name "GPIO14{slash}TXD") (class "Default")
      (node (ref "J41") (pin "8") (pinfunction "TX_8") (pintype "bidirectional"))
      (node (ref "UART2") (pin "5") (pinfunction "5:TX_5") (pintype "output"))
    )
    (net (code "17") (name "GPIO15{slash}RXD") (class "Default")
      (node (ref "J41") (pin "10") (pinfunction "RX_10") (pintype "bidirectional"))
      (node (ref "UART2") (pin "6") (pinfunction "6:RX_6") (pintype "input"))
    )
    (net (code "18") (name "GPIO16{slash}UART2_CTS") (class "Default")
      (node (ref "J41") (pin "36") (pinfunction "GPIO16_36") (pintype "bidirectional"))
      (node (ref "UART2") (pin "2") (pinfunction "2:CTS_2") (pintype "bidirectional"))
    )
    (net (code "19") (name "GPIO17{slash}UART2_RTS") (class "Default")
      (node (ref "J41") (pin "11") (pinfunction "GPIO17_11") (pintype "bidirectional"))
      (node (ref "UART2") (pin "4") (pinfunction "4:RTS_4") (pintype "bidirectional"))
    )
    (net (code "20") (name "GPIO18{slash}I2S0_SCLK") (class "Default")
      (node (ref "I2S0(DAP4)") (pin "4") (pinfunction "4:I2S_SCLK_4") (pintype "open_collector"))
      (node (ref "J41") (pin "12") (pinfunction "GPIO18_12") (pintype "bidirectional"))
    )
    (net (code "21") (name "GPIO19{slash}I2S0_FS") (class "Default")
      (node (ref "I2S0(DAP4)") (pin "2") (pinfunction "2:I2S_FS_2") (pintype "input"))
      (node (ref "J41") (pin "35") (pinfunction "GPIO19_35") (pintype "bidirectional"))
    )
    (net (code "22") (name "GPIO20{slash}I2S0_DIN") (class "Default")
      (node (ref "I2S0(DAP4)") (pin "5") (pinfunction "5:I2S_DIN_5") (pintype "input"))
      (node (ref "J41") (pin "38") (pinfunction "GPIO20_38") (pintype "bidirectional"))
    )
    (net (code "23") (name "GPIO21{slash}I2S0_DOUT") (class "Default")
      (node (ref "I2S0(DAP4)") (pin "6") (pinfunction "6:I2S_OUT_6") (pintype "output"))
      (node (ref "J41") (pin "40") (pinfunction "GPIO21_40") (pintype "bidirectional"))
    )
    (net (code "24") (name "GPIO22{slash}LCD_TE") (class "Default")
      (node (ref "GPIO5,6,22") (pin "4") (pinfunction "4:PIN-C_4") (pintype "bidirectional"))
      (node (ref "J41") (pin "15") (pinfunction "GPIO22_15") (pintype "bidirectional"))
    )
    (net (code "25") (name "GPIO23{slash}SPI2_CS1") (class "Default")
      (node (ref "J41") (pin "16") (pinfunction "GPIO23_16") (pintype "bidirectional"))
      (node (ref "SPI2-1") (pin "5") (pinfunction "5:CS_5") (pintype "open_collector"))
    )
    (net (code "26") (name "GPIO24{slash}SPI2_CS0") (class "Default")
      (node (ref "J41") (pin "18") (pinfunction "GPIO24_18") (pintype "bidirectional"))
      (node (ref "SPI2-0") (pin "5") (pinfunction "5:CS_5") (pintype "open_collector"))
    )
    (net (code "27") (name "GPIO25{slash}SPI2_MISO") (class "Default")
      (node (ref "J41") (pin "22") (pinfunction "GPIO25_22") (pintype "bidirectional"))
      (node (ref "SPI2-0") (pin "4") (pinfunction "4:MISO_4") (pintype "open_collector"))
      (node (ref "SPI2-1") (pin "4") (pinfunction "4:MISO_4") (pintype "open_collector"))
    )
    (net (code "28") (name "GPIO26{slash}SPI2_MOSI") (class "Default")
      (node (ref "J41") (pin "37") (pinfunction "GPIO26_37") (pintype "bidirectional"))
      (node (ref "SPI2-0") (pin "6") (pinfunction "6:MOSI_6") (pintype "open_collector"))
      (node (ref "SPI2-1") (pin "6") (pinfunction "6:MOSI_6") (pintype "open_collector"))
    )
    (net (code "29") (name "GPIO27{slash}SPI2_SCK") (class "Default")
      (node (ref "J41") (pin "13") (pinfunction "GPIO27_13") (pintype "bidirectional"))
      (node (ref "SPI2-0") (pin "2") (pinfunction "2:SCK_2") (pintype "open_collector"))
      (node (ref "SPI2-1") (pin "2") (pinfunction "2:SCK_2") (pintype "open_collector"))
    )
    (net (code "30") (name "I2C0_SCL") (class "Default")
      (node (ref "J41") (pin "28") (pinfunction "ID_SC_28") (pintype "bidirectional"))
    )
    (net (code "31") (name "I2C0_SDA") (class "Default")
      (node (ref "J41") (pin "27") (pinfunction "ID_SD_27") (pintype "bidirectional"))
    )
    (net (code "32") (name "NC1") (class "Default")
      (node (ref "J41") (pin "4") (pinfunction "5V_4") (pintype "bidirectional"))
    )
    (net (code "33") (name "NC2") (class "Default")
      (node (ref "J41") (pin "6") (pinfunction "GND_6") (pintype "bidirectional"))
    )
    (net (code "34") (name "Net-(GPIO4-3:VCC)") (class "Default")
      (node (ref "GPIO4") (pin "3") (pinfunction "3:VCC_3") (pintype "power_in"))
      (node (ref "U$32") (pin "2") (pinfunction "2_2") (pintype "bidirectional"))
    )
    (net (code "35") (name "Net-(GPIO4-5:PIN-A)") (class "Default")
      (node (ref "GPIO4") (pin "5") (pinfunction "5:PIN-A_5") (pintype "bidirectional"))
      (node (ref "SW-SEL1") (pin "5") (pinfunction "5_5") (pintype "passive"))
    )
    (net (code "36") (name "Net-(GPIO4-6:PIN-B)") (class "Default")
      (node (ref "GPIO4") (pin "6") (pinfunction "6:PIN-B_6") (pintype "bidirectional"))
      (node (ref "SW-SEL1") (pin "2") (pinfunction "2_2") (pintype "passive"))
    )
    (net (code "37") (name "Net-(GPIO5,6,22-3:VCC)") (class "Default")
      (node (ref "GPIO5,6,22") (pin "3") (pinfunction "3:VCC_3") (pintype "power_in"))
      (node (ref "U$3") (pin "2") (pinfunction "2_2") (pintype "bidirectional"))
    )
    (net (code "38") (name "unconnected-(GPIO4-2:NC-Pad2)") (class "Default")
      (node (ref "GPIO4") (pin "2") (pinfunction "2:NC_2") (pintype "no_connect"))
    )
    (net (code "39") (name "unconnected-(GPIO4-4:NC-Pad4)") (class "Default")
      (node (ref "GPIO4") (pin "4") (pinfunction "4:NC_4") (pintype "no_connect"))
    )
    (net (code "40") (name "unconnected-(GPIO5,6,22-2:NC-Pad2)") (class "Default")
      (node (ref "GPIO5,6,22") (pin "2") (pinfunction "2:NC_2") (pintype "no_connect"))
    )
    (net (code "41") (name "unconnected-(GPIO12,13PWM-2:NC-Pad2)") (class "Default")
      (node (ref "GPIO12,13PWM") (pin "2") (pinfunction "2:NC_2") (pintype "no_connect"))
    )
    (net (code "42") (name "unconnected-(GPIO12,13PWM-4:PIN-C-Pad4)") (class "Default")
      (node (ref "GPIO12,13PWM") (pin "4") (pinfunction "4:PIN-C_4") (pintype "bidirectional"))
    )
    (net (code "43") (name "unconnected-(I2C-2:NC-Pad2)") (class "Default")
      (node (ref "I2C") (pin "2") (pinfunction "2:NC_2") (pintype "no_connect"))
    )
    (net (code "44") (name "unconnected-(I2C-6:NC-Pad6)") (class "Default")
      (node (ref "I2C") (pin "6") (pinfunction "6:NC_6") (pintype "no_connect"))
    )
    (net (code "45") (name "unconnected-(I2C1-2:NC-Pad2)") (class "Default")
      (node (ref "I2C1") (pin "2") (pinfunction "2:NC_2") (pintype "no_connect"))
    )
    (net (code "46") (name "unconnected-(I2C1-6:NC-Pad6)") (class "Default")
      (node (ref "I2C1") (pin "6") (pinfunction "6:NC_6") (pintype "no_connect"))
    )
    (net (code "47") (name "unconnected-(SW-SEL1-Pad1)") (class "Default")
      (node (ref "SW-SEL1") (pin "1") (pinfunction "1_1") (pintype "passive"))
    )
    (net (code "48") (name "unconnected-(SW-SEL1-Pad3)") (class "Default")
      (node (ref "SW-SEL1") (pin "3") (pinfunction "3_3") (pintype "passive"))
    )
  )
)
